# CLK_DIST.net
KiCad netlist of a schematic drawn in Altium Designer
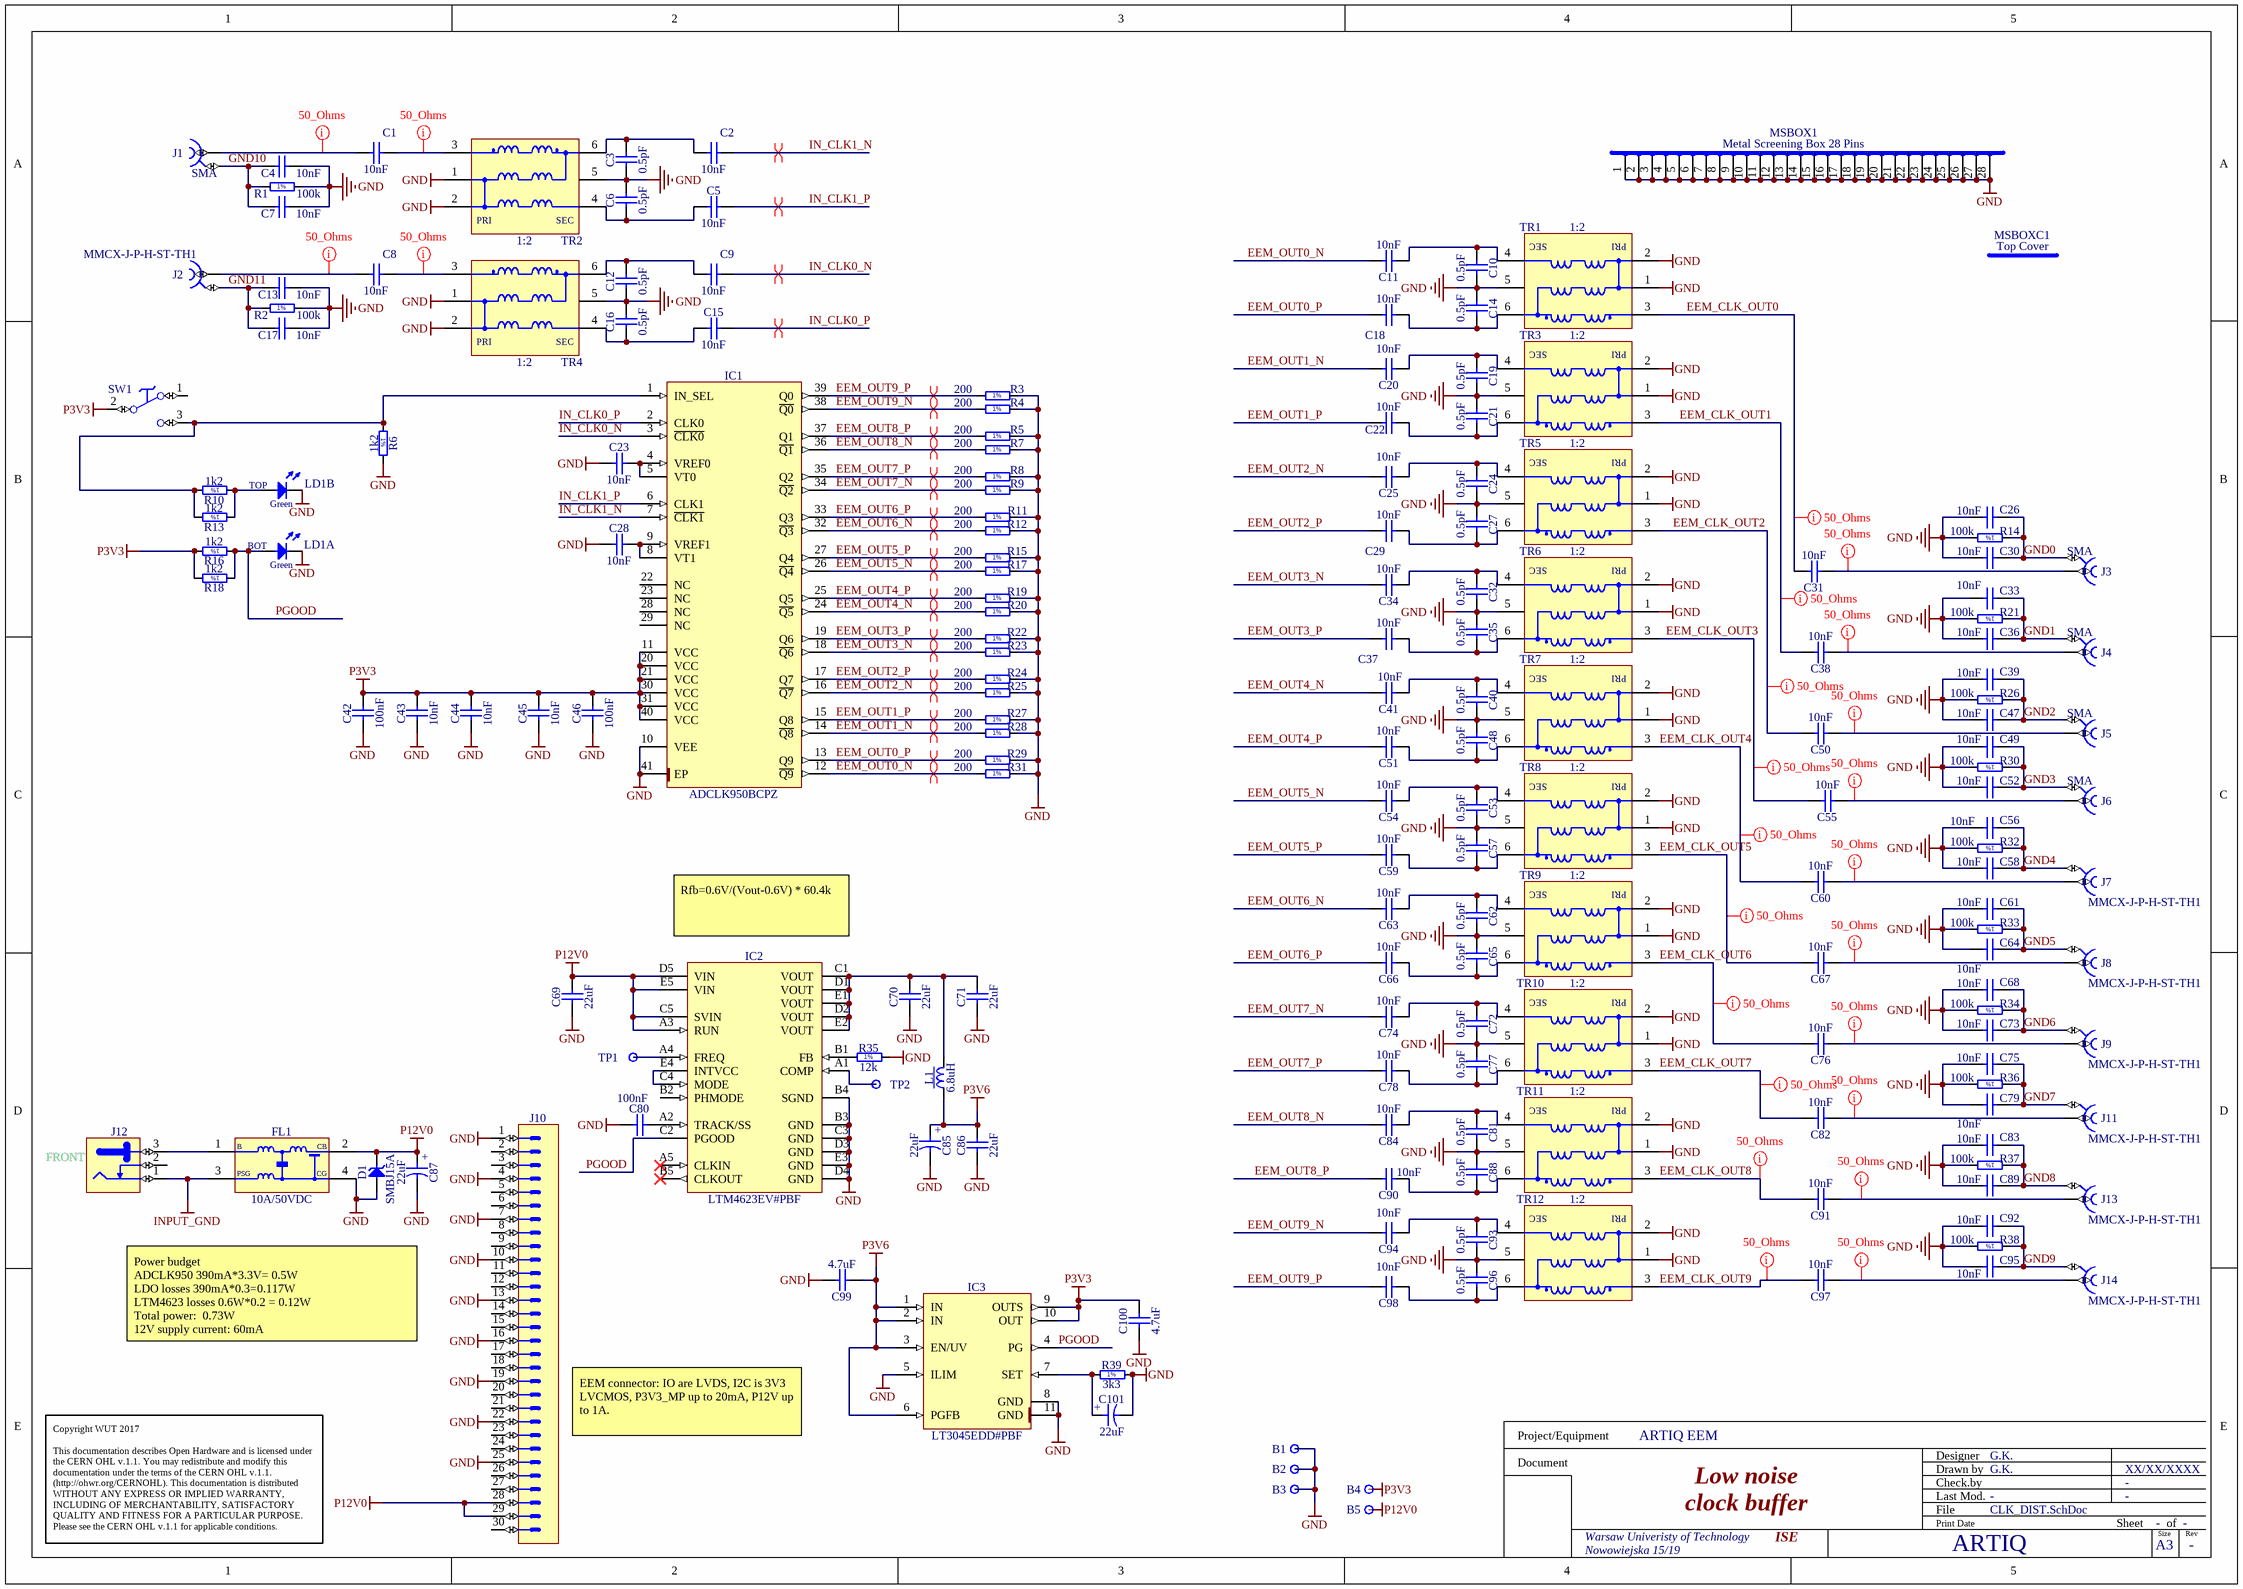
[diagram p0: CLK_DIST.SchDoc]

(export (version "E")
  (design (tool "Eeschema 10.0.6"))
  (components
    (comp (ref "B1")
      (value "Plated Hole")
      (footprint "c130h60")
      (description "Single Terminal Socket")
      (fields (field (name "PART NUMBER") "PLATED_HOLE0.6_PAD1.3") (field (name "AUTHOR") "CERN DEM MR"))
      (libsource (lib "Eletro-mechanical") (part "Single Terminal Socket"))
    )
    (comp (ref "B2")
      (value "Plated Hole")
      (footprint "c130h60")
      (description "Single Terminal Socket")
      (fields (field (name "PART NUMBER") "PLATED_HOLE0.6_PAD1.3") (field (name "AUTHOR") "CERN DEM MR"))
      (libsource (lib "Eletro-mechanical") (part "Single Terminal Socket"))
    )
    (comp (ref "B3")
      (value "Plated Hole")
      (footprint "c130h60")
      (description "Single Terminal Socket")
      (fields (field (name "PART NUMBER") "PLATED_HOLE0.6_PAD1.3") (field (name "AUTHOR") "CERN DEM MR"))
      (libsource (lib "Eletro-mechanical") (part "Single Terminal Socket"))
    )
    (comp (ref "B4")
      (value "Plated Hole")
      (footprint "c130h60")
      (description "Single Terminal Socket")
      (fields (field (name "PART NUMBER") "PLATED_HOLE0.6_PAD1.3") (field (name "AUTHOR") "CERN DEM MR"))
      (libsource (lib "Eletro-mechanical") (part "Single Terminal Socket"))
    )
    (comp (ref "B5")
      (value "Plated Hole")
      (footprint "c130h60")
      (description "Single Terminal Socket")
      (fields (field (name "PART NUMBER") "PLATED_HOLE0.6_PAD1.3") (field (name "AUTHOR") "CERN DEM MR"))
      (libsource (lib "Eletro-mechanical") (part "Single Terminal Socket"))
    )
    (comp (ref "C1")
      (value "10nF")
      (footprint "CAPC1608X87N")
      (description "Non-polarised capacitor")
      (fields
        (field (name "PART NUMBER") "CC0603_10NF_50V_5%_C0G")
        (field (name "VOLTAGE") "50V")
        (field (name "AUTHOR") "CERN DEM JLC")
      )
      (libsource (lib "Capacitors") (part "Capacitor - non polarized"))
    )
    (comp (ref "C2")
      (value "10nF")
      (footprint "CAPC1608X87N")
      (description "Non-polarised capacitor")
      (fields
        (field (name "PART NUMBER") "CC0603_10NF_50V_5%_C0G")
        (field (name "VOLTAGE") "50V")
        (field (name "AUTHOR") "CERN DEM JLC")
      )
      (libsource (lib "Capacitors") (part "Capacitor - non polarized"))
    )
    (comp (ref "C3")
      (value "0.5pF")
      (footprint "CAPC1005X50N")
      (description "Non-polarised capacitor")
      (fields
        (field (name "PART NUMBER") "CC0402_0.5PF_25V_0.05PF_AVX_04023J0R5ABSTR")
        (field (name "VOLTAGE") "25V")
        (field (name "AUTHOR") "CERN DEM JLC")
      )
      (libsource (lib "Capacitors") (part "Capacitor - non polarized"))
    )
    (comp (ref "C4")
      (value "10nF")
      (footprint "CAPC1608X87N")
      (description "Non-polarised capacitor")
      (fields
        (field (name "PART NUMBER") "CC0603_10NF_50V_5%_C0G")
        (field (name "VOLTAGE") "50V")
        (field (name "AUTHOR") "CERN DEM JLC")
      )
      (libsource (lib "Capacitors") (part "Capacitor - non polarized"))
    )
    (comp (ref "C5")
      (value "10nF")
      (footprint "CAPC1608X87N")
      (description "Non-polarised capacitor")
      (fields
        (field (name "PART NUMBER") "CC0603_10NF_50V_5%_C0G")
        (field (name "VOLTAGE") "50V")
        (field (name "AUTHOR") "CERN DEM JLC")
      )
      (libsource (lib "Capacitors") (part "Capacitor - non polarized"))
    )
    (comp (ref "C6")
      (value "0.5pF")
      (footprint "CAPC1005X50N")
      (description "Non-polarised capacitor")
      (fields
        (field (name "PART NUMBER") "CC0402_0.5PF_25V_0.05PF_AVX_04023J0R5ABSTR")
        (field (name "VOLTAGE") "25V")
        (field (name "AUTHOR") "CERN DEM JLC")
      )
      (libsource (lib "Capacitors") (part "Capacitor - non polarized"))
    )
    (comp (ref "C7")
      (value "10nF")
      (footprint "CAPC1608X87N")
      (description "Non-polarised capacitor")
      (fields
        (field (name "PART NUMBER") "CC0603_10NF_50V_5%_C0G")
        (field (name "VOLTAGE") "50V")
        (field (name "AUTHOR") "CERN DEM JLC")
      )
      (libsource (lib "Capacitors") (part "Capacitor - non polarized"))
    )
    (comp (ref "C8")
      (value "10nF")
      (footprint "CAPC1608X87N")
      (description "Non-polarised capacitor")
      (fields
        (field (name "PART NUMBER") "CC0603_10NF_50V_5%_C0G")
        (field (name "VOLTAGE") "50V")
        (field (name "AUTHOR") "CERN DEM JLC")
      )
      (libsource (lib "Capacitors") (part "Capacitor - non polarized"))
    )
    (comp (ref "C9")
      (value "10nF")
      (footprint "CAPC1608X87N")
      (description "Non-polarised capacitor")
      (fields
        (field (name "PART NUMBER") "CC0603_10NF_50V_5%_C0G")
        (field (name "VOLTAGE") "50V")
        (field (name "AUTHOR") "CERN DEM JLC")
      )
      (libsource (lib "Capacitors") (part "Capacitor - non polarized"))
    )
    (comp (ref "C10")
      (value "0.5pF")
      (footprint "CAPC1005X50N")
      (description "Non-polarised capacitor")
      (fields
        (field (name "PART NUMBER") "CC0402_0.5PF_25V_0.05PF_AVX_04023J0R5ABSTR")
        (field (name "VOLTAGE") "25V")
        (field (name "AUTHOR") "CERN DEM JLC")
      )
      (libsource (lib "Capacitors") (part "Capacitor - non polarized"))
    )
    (comp (ref "C11")
      (value "10nF")
      (footprint "CAPC1608X87N")
      (description "Non-polarised capacitor")
      (fields
        (field (name "PART NUMBER") "CC0603_10NF_50V_5%_C0G")
        (field (name "VOLTAGE") "50V")
        (field (name "AUTHOR") "CERN DEM JLC")
      )
      (libsource (lib "Capacitors") (part "Capacitor - non polarized"))
    )
    (comp (ref "C12")
      (value "0.5pF")
      (footprint "CAPC1005X50N")
      (description "Non-polarised capacitor")
      (fields
        (field (name "PART NUMBER") "CC0402_0.5PF_25V_0.05PF_AVX_04023J0R5ABSTR")
        (field (name "VOLTAGE") "25V")
        (field (name "AUTHOR") "CERN DEM JLC")
      )
      (libsource (lib "Capacitors") (part "Capacitor - non polarized"))
    )
    (comp (ref "C13")
      (value "10nF")
      (footprint "CAPC1608X87N")
      (description "Non-polarised capacitor")
      (fields
        (field (name "PART NUMBER") "CC0603_10NF_50V_5%_C0G")
        (field (name "VOLTAGE") "50V")
        (field (name "AUTHOR") "CERN DEM JLC")
      )
      (libsource (lib "Capacitors") (part "Capacitor - non polarized"))
    )
    (comp (ref "C14")
      (value "0.5pF")
      (footprint "CAPC1005X50N")
      (description "Non-polarised capacitor")
      (fields
        (field (name "PART NUMBER") "CC0402_0.5PF_25V_0.05PF_AVX_04023J0R5ABSTR")
        (field (name "VOLTAGE") "25V")
        (field (name "AUTHOR") "CERN DEM JLC")
      )
      (libsource (lib "Capacitors") (part "Capacitor - non polarized"))
    )
    (comp (ref "C15")
      (value "10nF")
      (footprint "CAPC1608X87N")
      (description "Non-polarised capacitor")
      (fields
        (field (name "PART NUMBER") "CC0603_10NF_50V_5%_C0G")
        (field (name "VOLTAGE") "50V")
        (field (name "AUTHOR") "CERN DEM JLC")
      )
      (libsource (lib "Capacitors") (part "Capacitor - non polarized"))
    )
    (comp (ref "C16")
      (value "0.5pF")
      (footprint "CAPC1005X50N")
      (description "Non-polarised capacitor")
      (fields
        (field (name "PART NUMBER") "CC0402_0.5PF_25V_0.05PF_AVX_04023J0R5ABSTR")
        (field (name "VOLTAGE") "25V")
        (field (name "AUTHOR") "CERN DEM JLC")
      )
      (libsource (lib "Capacitors") (part "Capacitor - non polarized"))
    )
    (comp (ref "C17")
      (value "10nF")
      (footprint "CAPC1608X87N")
      (description "Non-polarised capacitor")
      (fields
        (field (name "PART NUMBER") "CC0603_10NF_50V_5%_C0G")
        (field (name "VOLTAGE") "50V")
        (field (name "AUTHOR") "CERN DEM JLC")
      )
      (libsource (lib "Capacitors") (part "Capacitor - non polarized"))
    )
    (comp (ref "C18")
      (value "10nF")
      (footprint "CAPC1608X87N")
      (description "Non-polarised capacitor")
      (fields
        (field (name "PART NUMBER") "CC0603_10NF_50V_5%_C0G")
        (field (name "VOLTAGE") "50V")
        (field (name "AUTHOR") "CERN DEM JLC")
      )
      (libsource (lib "Capacitors") (part "Capacitor - non polarized"))
    )
    (comp (ref "C19")
      (value "0.5pF")
      (footprint "CAPC1005X50N")
      (description "Non-polarised capacitor")
      (fields
        (field (name "PART NUMBER") "CC0402_0.5PF_25V_0.05PF_AVX_04023J0R5ABSTR")
        (field (name "VOLTAGE") "25V")
        (field (name "AUTHOR") "CERN DEM JLC")
      )
      (libsource (lib "Capacitors") (part "Capacitor - non polarized"))
    )
    (comp (ref "C20")
      (value "10nF")
      (footprint "CAPC1608X87N")
      (description "Non-polarised capacitor")
      (fields
        (field (name "PART NUMBER") "CC0603_10NF_50V_5%_C0G")
        (field (name "VOLTAGE") "50V")
        (field (name "AUTHOR") "CERN DEM JLC")
      )
      (libsource (lib "Capacitors") (part "Capacitor - non polarized"))
    )
    (comp (ref "C21")
      (value "0.5pF")
      (footprint "CAPC1005X50N")
      (description "Non-polarised capacitor")
      (fields
        (field (name "PART NUMBER") "CC0402_0.5PF_25V_0.05PF_AVX_04023J0R5ABSTR")
        (field (name "VOLTAGE") "25V")
        (field (name "AUTHOR") "CERN DEM JLC")
      )
      (libsource (lib "Capacitors") (part "Capacitor - non polarized"))
    )
    (comp (ref "C22")
      (value "10nF")
      (footprint "CAPC1608X87N")
      (description "Non-polarised capacitor")
      (fields
        (field (name "PART NUMBER") "CC0603_10NF_50V_5%_C0G")
        (field (name "VOLTAGE") "50V")
        (field (name "AUTHOR") "CERN DEM JLC")
      )
      (libsource (lib "Capacitors") (part "Capacitor - non polarized"))
    )
    (comp (ref "C23")
      (value "10nF")
      (footprint "CAPC1608X87N")
      (description "Non-polarised capacitor")
      (fields
        (field (name "PART NUMBER") "CC0603_10NF_50V_5%_C0G")
        (field (name "VOLTAGE") "50V")
        (field (name "AUTHOR") "CERN DEM JLC")
      )
      (libsource (lib "Capacitors") (part "Capacitor - non polarized"))
    )
    (comp (ref "C24")
      (value "0.5pF")
      (footprint "CAPC1005X50N")
      (description "Non-polarised capacitor")
      (fields
        (field (name "PART NUMBER") "CC0402_0.5PF_25V_0.05PF_AVX_04023J0R5ABSTR")
        (field (name "VOLTAGE") "25V")
        (field (name "AUTHOR") "CERN DEM JLC")
      )
      (libsource (lib "Capacitors") (part "Capacitor - non polarized"))
    )
    (comp (ref "C25")
      (value "10nF")
      (footprint "CAPC1608X87N")
      (description "Non-polarised capacitor")
      (fields
        (field (name "PART NUMBER") "CC0603_10NF_50V_5%_C0G")
        (field (name "VOLTAGE") "50V")
        (field (name "AUTHOR") "CERN DEM JLC")
      )
      (libsource (lib "Capacitors") (part "Capacitor - non polarized"))
    )
    (comp (ref "C26")
      (value "10nF")
      (footprint "CAPC1608X87N")
      (description "Non-polarised capacitor")
      (fields
        (field (name "PART NUMBER") "CC0603_10NF_50V_5%_C0G")
        (field (name "VOLTAGE") "50V")
        (field (name "AUTHOR") "CERN DEM JLC")
      )
      (libsource (lib "Capacitors") (part "Capacitor - non polarized"))
    )
    (comp (ref "C27")
      (value "0.5pF")
      (footprint "CAPC1005X50N")
      (description "Non-polarised capacitor")
      (fields
        (field (name "PART NUMBER") "CC0402_0.5PF_25V_0.05PF_AVX_04023J0R5ABSTR")
        (field (name "VOLTAGE") "25V")
        (field (name "AUTHOR") "CERN DEM JLC")
      )
      (libsource (lib "Capacitors") (part "Capacitor - non polarized"))
    )
    (comp (ref "C28")
      (value "10nF")
      (footprint "CAPC1608X87N")
      (description "Non-polarised capacitor")
      (fields
        (field (name "PART NUMBER") "CC0603_10NF_50V_5%_C0G")
        (field (name "VOLTAGE") "50V")
        (field (name "AUTHOR") "CERN DEM JLC")
      )
      (libsource (lib "Capacitors") (part "Capacitor - non polarized"))
    )
    (comp (ref "C29")
      (value "10nF")
      (footprint "CAPC1608X87N")
      (description "Non-polarised capacitor")
      (fields
        (field (name "PART NUMBER") "CC0603_10NF_50V_5%_C0G")
        (field (name "VOLTAGE") "50V")
        (field (name "AUTHOR") "CERN DEM JLC")
      )
      (libsource (lib "Capacitors") (part "Capacitor - non polarized"))
    )
    (comp (ref "C30")
      (value "10nF")
      (footprint "CAPC1608X87N")
      (description "Non-polarised capacitor")
      (fields
        (field (name "PART NUMBER") "CC0603_10NF_50V_5%_C0G")
        (field (name "VOLTAGE") "50V")
        (field (name "AUTHOR") "CERN DEM JLC")
      )
      (libsource (lib "Capacitors") (part "Capacitor - non polarized"))
    )
    (comp (ref "C31")
      (value "10nF")
      (footprint "CAPC1608X87N")
      (description "Non-polarised capacitor")
      (fields
        (field (name "PART NUMBER") "CC0603_10NF_50V_5%_C0G")
        (field (name "VOLTAGE") "50V")
        (field (name "AUTHOR") "CERN DEM JLC")
      )
      (libsource (lib "Capacitors") (part "Capacitor - non polarized"))
    )
    (comp (ref "C32")
      (value "0.5pF")
      (footprint "CAPC1005X50N")
      (description "Non-polarised capacitor")
      (fields
        (field (name "PART NUMBER") "CC0402_0.5PF_25V_0.05PF_AVX_04023J0R5ABSTR")
        (field (name "VOLTAGE") "25V")
        (field (name "AUTHOR") "CERN DEM JLC")
      )
      (libsource (lib "Capacitors") (part "Capacitor - non polarized"))
    )
    (comp (ref "C33")
      (value "10nF")
      (footprint "CAPC1608X87N")
      (description "Non-polarised capacitor")
      (fields
        (field (name "PART NUMBER") "CC0603_10NF_50V_5%_C0G")
        (field (name "VOLTAGE") "50V")
        (field (name "AUTHOR") "CERN DEM JLC")
      )
      (libsource (lib "Capacitors") (part "Capacitor - non polarized"))
    )
    (comp (ref "C34")
      (value "10nF")
      (footprint "CAPC1608X87N")
      (description "Non-polarised capacitor")
      (fields
        (field (name "PART NUMBER") "CC0603_10NF_50V_5%_C0G")
        (field (name "VOLTAGE") "50V")
        (field (name "AUTHOR") "CERN DEM JLC")
      )
      (libsource (lib "Capacitors") (part "Capacitor - non polarized"))
    )
    (comp (ref "C35")
      (value "0.5pF")
      (footprint "CAPC1005X50N")
      (description "Non-polarised capacitor")
      (fields
        (field (name "PART NUMBER") "CC0402_0.5PF_25V_0.05PF_AVX_04023J0R5ABSTR")
        (field (name "VOLTAGE") "25V")
        (field (name "AUTHOR") "CERN DEM JLC")
      )
      (libsource (lib "Capacitors") (part "Capacitor - non polarized"))
    )
    (comp (ref "C36")
      (value "10nF")
      (footprint "CAPC1608X87N")
      (description "Non-polarised capacitor")
      (fields
        (field (name "PART NUMBER") "CC0603_10NF_50V_5%_C0G")
        (field (name "VOLTAGE") "50V")
        (field (name "AUTHOR") "CERN DEM JLC")
      )
      (libsource (lib "Capacitors") (part "Capacitor - non polarized"))
    )
    (comp (ref "C37")
      (value "10nF")
      (footprint "CAPC1608X87N")
      (description "Non-polarised capacitor")
      (fields
        (field (name "PART NUMBER") "CC0603_10NF_50V_5%_C0G")
        (field (name "VOLTAGE") "50V")
        (field (name "AUTHOR") "CERN DEM JLC")
      )
      (libsource (lib "Capacitors") (part "Capacitor - non polarized"))
    )
    (comp (ref "C38")
      (value "10nF")
      (footprint "CAPC1608X87N")
      (description "Non-polarised capacitor")
      (fields
        (field (name "PART NUMBER") "CC0603_10NF_50V_5%_C0G")
        (field (name "VOLTAGE") "50V")
        (field (name "AUTHOR") "CERN DEM JLC")
      )
      (libsource (lib "Capacitors") (part "Capacitor - non polarized"))
    )
    (comp (ref "C39")
      (value "10nF")
      (footprint "CAPC1608X87N")
      (description "Non-polarised capacitor")
      (fields
        (field (name "PART NUMBER") "CC0603_10NF_50V_5%_C0G")
        (field (name "VOLTAGE") "50V")
        (field (name "AUTHOR") "CERN DEM JLC")
      )
      (libsource (lib "Capacitors") (part "Capacitor - non polarized"))
    )
    (comp (ref "C40")
      (value "0.5pF")
      (footprint "CAPC1005X50N")
      (description "Non-polarised capacitor")
      (fields
        (field (name "PART NUMBER") "CC0402_0.5PF_25V_0.05PF_AVX_04023J0R5ABSTR")
        (field (name "VOLTAGE") "25V")
        (field (name "AUTHOR") "CERN DEM JLC")
      )
      (libsource (lib "Capacitors") (part "Capacitor - non polarized"))
    )
    (comp (ref "C41")
      (value "10nF")
      (footprint "CAPC1608X87N")
      (description "Non-polarised capacitor")
      (fields
        (field (name "PART NUMBER") "CC0603_10NF_50V_5%_C0G")
        (field (name "VOLTAGE") "50V")
        (field (name "AUTHOR") "CERN DEM JLC")
      )
      (libsource (lib "Capacitors") (part "Capacitor - non polarized"))
    )
    (comp (ref "C42")
      (value "100nF")
      (footprint "CAPC1005X55N")
      (description "Non-polarised capacitor")
      (fields
        (field (name "PART NUMBER") "CC0402_100NF_16V_10%_X5R")
        (field (name "VOLTAGE") "16V")
        (field (name "AUTHOR") "CERN DEM JLC")
      )
      (libsource (lib "Capacitors") (part "Capacitor - non polarized"))
    )
    (comp (ref "C43")
      (value "10nF")
      (footprint "CAPC1608X87N")
      (description "Non-polarised capacitor")
      (fields
        (field (name "PART NUMBER") "CC0603_10NF_50V_5%_C0G")
        (field (name "VOLTAGE") "50V")
        (field (name "AUTHOR") "CERN DEM JLC")
      )
      (libsource (lib "Capacitors") (part "Capacitor - non polarized"))
    )
    (comp (ref "C44")
      (value "10nF")
      (footprint "CAPC1608X87N")
      (description "Non-polarised capacitor")
      (fields
        (field (name "PART NUMBER") "CC0603_10NF_50V_5%_C0G")
        (field (name "VOLTAGE") "50V")
        (field (name "AUTHOR") "CERN DEM JLC")
      )
      (libsource (lib "Capacitors") (part "Capacitor - non polarized"))
    )
    (comp (ref "C45")
      (value "10nF")
      (footprint "CAPC1608X87N")
      (description "Non-polarised capacitor")
      (fields
        (field (name "PART NUMBER") "CC0603_10NF_50V_5%_C0G")
        (field (name "VOLTAGE") "50V")
        (field (name "AUTHOR") "CERN DEM JLC")
      )
      (libsource (lib "Capacitors") (part "Capacitor - non polarized"))
    )
    (comp (ref "C46")
      (value "100nF")
      (footprint "CAPC1005X55N")
      (description "Non-polarised capacitor")
      (fields
        (field (name "PART NUMBER") "CC0402_100NF_16V_10%_X5R")
        (field (name "VOLTAGE") "16V")
        (field (name "AUTHOR") "CERN DEM JLC")
      )
      (libsource (lib "Capacitors") (part "Capacitor - non polarized"))
    )
    (comp (ref "C47")
      (value "10nF")
      (footprint "CAPC1608X87N")
      (description "Non-polarised capacitor")
      (fields
        (field (name "PART NUMBER") "CC0603_10NF_50V_5%_C0G")
        (field (name "VOLTAGE") "50V")
        (field (name "AUTHOR") "CERN DEM JLC")
      )
      (libsource (lib "Capacitors") (part "Capacitor - non polarized"))
    )
    (comp (ref "C48")
      (value "0.5pF")
      (footprint "CAPC1005X50N")
      (description "Non-polarised capacitor")
      (fields
        (field (name "PART NUMBER") "CC0402_0.5PF_25V_0.05PF_AVX_04023J0R5ABSTR")
        (field (name "VOLTAGE") "25V")
        (field (name "AUTHOR") "CERN DEM JLC")
      )
      (libsource (lib "Capacitors") (part "Capacitor - non polarized"))
    )
    (comp (ref "C49")
      (value "10nF")
      (footprint "CAPC1608X87N")
      (description "Non-polarised capacitor")
      (fields
        (field (name "PART NUMBER") "CC0603_10NF_50V_5%_C0G")
        (field (name "VOLTAGE") "50V")
        (field (name "AUTHOR") "CERN DEM JLC")
      )
      (libsource (lib "Capacitors") (part "Capacitor - non polarized"))
    )
    (comp (ref "C50")
      (value "10nF")
      (footprint "CAPC1608X87N")
      (description "Non-polarised capacitor")
      (fields
        (field (name "PART NUMBER") "CC0603_10NF_50V_5%_C0G")
        (field (name "VOLTAGE") "50V")
        (field (name "AUTHOR") "CERN DEM JLC")
      )
      (libsource (lib "Capacitors") (part "Capacitor - non polarized"))
    )
    (comp (ref "C51")
      (value "10nF")
      (footprint "CAPC1608X87N")
      (description "Non-polarised capacitor")
      (fields
        (field (name "PART NUMBER") "CC0603_10NF_50V_5%_C0G")
        (field (name "VOLTAGE") "50V")
        (field (name "AUTHOR") "CERN DEM JLC")
      )
      (libsource (lib "Capacitors") (part "Capacitor - non polarized"))
    )
    (comp (ref "C52")
      (value "10nF")
      (footprint "CAPC1608X87N")
      (description "Non-polarised capacitor")
      (fields
        (field (name "PART NUMBER") "CC0603_10NF_50V_5%_C0G")
        (field (name "VOLTAGE") "50V")
        (field (name "AUTHOR") "CERN DEM JLC")
      )
      (libsource (lib "Capacitors") (part "Capacitor - non polarized"))
    )
    (comp (ref "C53")
      (value "0.5pF")
      (footprint "CAPC1005X50N")
      (description "Non-polarised capacitor")
      (fields
        (field (name "PART NUMBER") "CC0402_0.5PF_25V_0.05PF_AVX_04023J0R5ABSTR")
        (field (name "VOLTAGE") "25V")
        (field (name "AUTHOR") "CERN DEM JLC")
      )
      (libsource (lib "Capacitors") (part "Capacitor - non polarized"))
    )
    (comp (ref "C54")
      (value "10nF")
      (footprint "CAPC1608X87N")
      (description "Non-polarised capacitor")
      (fields
        (field (name "PART NUMBER") "CC0603_10NF_50V_5%_C0G")
        (field (name "VOLTAGE") "50V")
        (field (name "AUTHOR") "CERN DEM JLC")
      )
      (libsource (lib "Capacitors") (part "Capacitor - non polarized"))
    )
    (comp (ref "C55")
      (value "10nF")
      (footprint "CAPC1608X87N")
      (description "Non-polarised capacitor")
      (fields
        (field (name "PART NUMBER") "CC0603_10NF_50V_5%_C0G")
        (field (name "VOLTAGE") "50V")
        (field (name "AUTHOR") "CERN DEM JLC")
      )
      (libsource (lib "Capacitors") (part "Capacitor - non polarized"))
    )
    (comp (ref "C56")
      (value "10nF")
      (footprint "CAPC1608X87N")
      (description "Non-polarised capacitor")
      (fields
        (field (name "PART NUMBER") "CC0603_10NF_50V_5%_C0G")
        (field (name "VOLTAGE") "50V")
        (field (name "AUTHOR") "CERN DEM JLC")
      )
      (libsource (lib "Capacitors") (part "Capacitor - non polarized"))
    )
    (comp (ref "C57")
      (value "0.5pF")
      (footprint "CAPC1005X50N")
      (description "Non-polarised capacitor")
      (fields
        (field (name "PART NUMBER") "CC0402_0.5PF_25V_0.05PF_AVX_04023J0R5ABSTR")
        (field (name "VOLTAGE") "25V")
        (field (name "AUTHOR") "CERN DEM JLC")
      )
      (libsource (lib "Capacitors") (part "Capacitor - non polarized"))
    )
    (comp (ref "C58")
      (value "10nF")
      (footprint "CAPC1608X87N")
      (description "Non-polarised capacitor")
      (fields
        (field (name "PART NUMBER") "CC0603_10NF_50V_5%_C0G")
        (field (name "VOLTAGE") "50V")
        (field (name "AUTHOR") "CERN DEM JLC")
      )
      (libsource (lib "Capacitors") (part "Capacitor - non polarized"))
    )
    (comp (ref "C59")
      (value "10nF")
      (footprint "CAPC1608X87N")
      (description "Non-polarised capacitor")
      (fields
        (field (name "PART NUMBER") "CC0603_10NF_50V_5%_C0G")
        (field (name "VOLTAGE") "50V")
        (field (name "AUTHOR") "CERN DEM JLC")
      )
      (libsource (lib "Capacitors") (part "Capacitor - non polarized"))
    )
    (comp (ref "C60")
      (value "10nF")
      (footprint "CAPC1608X87N")
      (description "Non-polarised capacitor")
      (fields
        (field (name "PART NUMBER") "CC0603_10NF_50V_5%_C0G")
        (field (name "VOLTAGE") "50V")
        (field (name "AUTHOR") "CERN DEM JLC")
      )
      (libsource (lib "Capacitors") (part "Capacitor - non polarized"))
    )
    (comp (ref "C61")
      (value "10nF")
      (footprint "CAPC1608X87N")
      (description "Non-polarised capacitor")
      (fields
        (field (name "PART NUMBER") "CC0603_10NF_50V_5%_C0G")
        (field (name "VOLTAGE") "50V")
        (field (name "AUTHOR") "CERN DEM JLC")
      )
      (libsource (lib "Capacitors") (part "Capacitor - non polarized"))
    )
    (comp (ref "C62")
      (value "0.5pF")
      (footprint "CAPC1005X50N")
      (description "Non-polarised capacitor")
      (fields
        (field (name "PART NUMBER") "CC0402_0.5PF_25V_0.05PF_AVX_04023J0R5ABSTR")
        (field (name "VOLTAGE") "25V")
        (field (name "AUTHOR") "CERN DEM JLC")
      )
      (libsource (lib "Capacitors") (part "Capacitor - non polarized"))
    )
    (comp (ref "C63")
      (value "10nF")
      (footprint "CAPC1608X87N")
      (description "Non-polarised capacitor")
      (fields
        (field (name "PART NUMBER") "CC0603_10NF_50V_5%_C0G")
        (field (name "VOLTAGE") "50V")
        (field (name "AUTHOR") "CERN DEM JLC")
      )
      (libsource (lib "Capacitors") (part "Capacitor - non polarized"))
    )
    (comp (ref "C64")
      (value "10nF")
      (footprint "CAPC1608X87N")
      (description "Non-polarised capacitor")
      (fields
        (field (name "PART NUMBER") "CC0603_10NF_50V_5%_C0G")
        (field (name "VOLTAGE") "50V")
        (field (name "AUTHOR") "CERN DEM JLC")
      )
      (libsource (lib "Capacitors") (part "Capacitor - non polarized"))
    )
    (comp (ref "C65")
      (value "0.5pF")
      (footprint "CAPC1005X50N")
      (description "Non-polarised capacitor")
      (fields
        (field (name "PART NUMBER") "CC0402_0.5PF_25V_0.05PF_AVX_04023J0R5ABSTR")
        (field (name "VOLTAGE") "25V")
        (field (name "AUTHOR") "CERN DEM JLC")
      )
      (libsource (lib "Capacitors") (part "Capacitor - non polarized"))
    )
    (comp (ref "C66")
      (value "10nF")
      (footprint "CAPC1608X87N")
      (description "Non-polarised capacitor")
      (fields
        (field (name "PART NUMBER") "CC0603_10NF_50V_5%_C0G")
        (field (name "VOLTAGE") "50V")
        (field (name "AUTHOR") "CERN DEM JLC")
      )
      (libsource (lib "Capacitors") (part "Capacitor - non polarized"))
    )
    (comp (ref "C67")
      (value "10nF")
      (footprint "CAPC1608X87N")
      (description "Non-polarised capacitor")
      (fields
        (field (name "PART NUMBER") "CC0603_10NF_50V_5%_C0G")
        (field (name "VOLTAGE") "50V")
        (field (name "AUTHOR") "CERN DEM JLC")
      )
      (libsource (lib "Capacitors") (part "Capacitor - non polarized"))
    )
    (comp (ref "C68")
      (value "10nF")
      (footprint "CAPC1608X87N")
      (description "Non-polarised capacitor")
      (fields
        (field (name "PART NUMBER") "CC0603_10NF_50V_5%_C0G")
        (field (name "VOLTAGE") "50V")
        (field (name "AUTHOR") "CERN DEM JLC")
      )
      (libsource (lib "Capacitors") (part "Capacitor - non polarized"))
    )
    (comp (ref "C69")
      (value "22uF")
      (footprint "CAPC2012X135N")
      (description "Non-polarised capacitor")
      (fields
        (field (name "PART NUMBER") "CC0805_22UF_16V_10%_X5R")
        (field (name "VOLTAGE") "16V")
        (field (name "AUTHOR") "CERN DEM JLC")
      )
      (libsource (lib "Capacitors") (part "Capacitor - non polarized"))
    )
    (comp (ref "C70")
      (value "22uF")
      (footprint "CAPC2012X135N")
      (description "Non-polarised capacitor")
      (fields
        (field (name "PART NUMBER") "CC0805_22UF_16V_10%_X5R")
        (field (name "VOLTAGE") "16V")
        (field (name "AUTHOR") "CERN DEM JLC")
      )
      (libsource (lib "Capacitors") (part "Capacitor - non polarized"))
    )
    (comp (ref "C71")
      (value "22uF")
      (footprint "CAPC2012X135N")
      (description "Non-polarised capacitor")
      (fields
        (field (name "PART NUMBER") "CC0805_22UF_16V_10%_X5R")
        (field (name "VOLTAGE") "16V")
        (field (name "AUTHOR") "CERN DEM JLC")
      )
      (libsource (lib "Capacitors") (part "Capacitor - non polarized"))
    )
    (comp (ref "C72")
      (value "0.5pF")
      (footprint "CAPC1005X50N")
      (description "Non-polarised capacitor")
      (fields
        (field (name "PART NUMBER") "CC0402_0.5PF_25V_0.05PF_AVX_04023J0R5ABSTR")
        (field (name "VOLTAGE") "25V")
        (field (name "AUTHOR") "CERN DEM JLC")
      )
      (libsource (lib "Capacitors") (part "Capacitor - non polarized"))
    )
    (comp (ref "C73")
      (value "10nF")
      (footprint "CAPC1608X87N")
      (description "Non-polarised capacitor")
      (fields
        (field (name "PART NUMBER") "CC0603_10NF_50V_5%_C0G")
        (field (name "VOLTAGE") "50V")
        (field (name "AUTHOR") "CERN DEM JLC")
      )
      (libsource (lib "Capacitors") (part "Capacitor - non polarized"))
    )
    (comp (ref "C74")
      (value "10nF")
      (footprint "CAPC1608X87N")
      (description "Non-polarised capacitor")
      (fields
        (field (name "PART NUMBER") "CC0603_10NF_50V_5%_C0G")
        (field (name "VOLTAGE") "50V")
        (field (name "AUTHOR") "CERN DEM JLC")
      )
      (libsource (lib "Capacitors") (part "Capacitor - non polarized"))
    )
    (comp (ref "C75")
      (value "10nF")
      (footprint "CAPC1608X87N")
      (description "Non-polarised capacitor")
      (fields
        (field (name "PART NUMBER") "CC0603_10NF_50V_5%_C0G")
        (field (name "VOLTAGE") "50V")
        (field (name "AUTHOR") "CERN DEM JLC")
      )
      (libsource (lib "Capacitors") (part "Capacitor - non polarized"))
    )
    (comp (ref "C76")
      (value "10nF")
      (footprint "CAPC1608X87N")
      (description "Non-polarised capacitor")
      (fields
        (field (name "PART NUMBER") "CC0603_10NF_50V_5%_C0G")
        (field (name "VOLTAGE") "50V")
        (field (name "AUTHOR") "CERN DEM JLC")
      )
      (libsource (lib "Capacitors") (part "Capacitor - non polarized"))
    )
    (comp (ref "C77")
      (value "0.5pF")
      (footprint "CAPC1005X50N")
      (description "Non-polarised capacitor")
      (fields
        (field (name "PART NUMBER") "CC0402_0.5PF_25V_0.05PF_AVX_04023J0R5ABSTR")
        (field (name "VOLTAGE") "25V")
        (field (name "AUTHOR") "CERN DEM JLC")
      )
      (libsource (lib "Capacitors") (part "Capacitor - non polarized"))
    )
    (comp (ref "C78")
      (value "10nF")
      (footprint "CAPC1608X87N")
      (description "Non-polarised capacitor")
      (fields
        (field (name "PART NUMBER") "CC0603_10NF_50V_5%_C0G")
        (field (name "VOLTAGE") "50V")
        (field (name "AUTHOR") "CERN DEM JLC")
      )
      (libsource (lib "Capacitors") (part "Capacitor - non polarized"))
    )
    (comp (ref "C79")
      (value "10nF")
      (footprint "CAPC1608X87N")
      (description "Non-polarised capacitor")
      (fields
        (field (name "PART NUMBER") "CC0603_10NF_50V_5%_C0G")
        (field (name "VOLTAGE") "50V")
        (field (name "AUTHOR") "CERN DEM JLC")
      )
      (libsource (lib "Capacitors") (part "Capacitor - non polarized"))
    )
    (comp (ref "C80")
      (value "100nF")
      (footprint "CAPC1005X55N")
      (description "Non-polarised capacitor")
      (fields
        (field (name "PART NUMBER") "CC0402_100NF_16V_10%_X5R")
        (field (name "VOLTAGE") "16V")
        (field (name "AUTHOR") "CERN DEM JLC")
      )
      (libsource (lib "Capacitors") (part "Capacitor - non polarized"))
    )
    (comp (ref "C81")
      (value "0.5pF")
      (footprint "CAPC1005X50N")
      (description "Non-polarised capacitor")
      (fields
        (field (name "PART NUMBER") "CC0402_0.5PF_25V_0.05PF_AVX_04023J0R5ABSTR")
        (field (name "VOLTAGE") "25V")
        (field (name "AUTHOR") "CERN DEM JLC")
      )
      (libsource (lib "Capacitors") (part "Capacitor - non polarized"))
    )
    (comp (ref "C82")
      (value "10nF")
      (footprint "CAPC1608X87N")
      (description "Non-polarised capacitor")
      (fields
        (field (name "PART NUMBER") "CC0603_10NF_50V_5%_C0G")
        (field (name "VOLTAGE") "50V")
        (field (name "AUTHOR") "CERN DEM JLC")
      )
      (libsource (lib "Capacitors") (part "Capacitor - non polarized"))
    )
    (comp (ref "C83")
      (value "10nF")
      (footprint "CAPC1608X87N")
      (description "Non-polarised capacitor")
      (fields
        (field (name "PART NUMBER") "CC0603_10NF_50V_5%_C0G")
        (field (name "VOLTAGE") "50V")
        (field (name "AUTHOR") "CERN DEM JLC")
      )
      (libsource (lib "Capacitors") (part "Capacitor - non polarized"))
    )
    (comp (ref "C84")
      (value "10nF")
      (footprint "CAPC1608X87N")
      (description "Non-polarised capacitor")
      (fields
        (field (name "PART NUMBER") "CC0603_10NF_50V_5%_C0G")
        (field (name "VOLTAGE") "50V")
        (field (name "AUTHOR") "CERN DEM JLC")
      )
      (libsource (lib "Capacitors") (part "Capacitor - non polarized"))
    )
    (comp (ref "C85")
      (value "22uF")
      (footprint "CAPMP3216X180N")
      (description "Polarised capacitor")
      (fields
        (field (name "PART NUMBER") "CTE3216-18_22UF_6.3V_10%_LESR0900")
        (field (name "VOLTAGE") "6.3V")
        (field (name "AUTHOR") "CERN DEM JLC")
      )
      (libsource (lib "Capacitors") (part "Capacitor - polarized"))
    )
    (comp (ref "C86")
      (value "22uF")
      (footprint "CAPC2012X135N")
      (description "Non-polarised capacitor")
      (fields
        (field (name "PART NUMBER") "CC0805_22UF_16V_10%_X5R")
        (field (name "VOLTAGE") "16V")
        (field (name "AUTHOR") "CERN DEM JLC")
      )
      (libsource (lib "Capacitors") (part "Capacitor - non polarized"))
    )
    (comp (ref "C87")
      (value "22uF")
      (footprint "CAPAE530X540N")
      (description "Polarised capacitor")
      (fields
        (field (name "PART NUMBER") "CAE530-540_22UF_16V_20%")
        (field (name "VOLTAGE") "16V")
        (field (name "AUTHOR") "CERN DEM JLC")
      )
      (libsource (lib "Capacitors") (part "Capacitor - polarized"))
    )
    (comp (ref "C88")
      (value "0.5pF")
      (footprint "CAPC1005X50N")
      (description "Non-polarised capacitor")
      (fields
        (field (name "PART NUMBER") "CC0402_0.5PF_25V_0.05PF_AVX_04023J0R5ABSTR")
        (field (name "VOLTAGE") "25V")
        (field (name "AUTHOR") "CERN DEM JLC")
      )
      (libsource (lib "Capacitors") (part "Capacitor - non polarized"))
    )
    (comp (ref "C89")
      (value "10nF")
      (footprint "CAPC1608X87N")
      (description "Non-polarised capacitor")
      (fields
        (field (name "PART NUMBER") "CC0603_10NF_50V_5%_C0G")
        (field (name "VOLTAGE") "50V")
        (field (name "AUTHOR") "CERN DEM JLC")
      )
      (libsource (lib "Capacitors") (part "Capacitor - non polarized"))
    )
    (comp (ref "C90")
      (value "10nF")
      (footprint "CAPC1608X87N")
      (description "Non-polarised capacitor")
      (fields
        (field (name "PART NUMBER") "CC0603_10NF_50V_5%_C0G")
        (field (name "VOLTAGE") "50V")
        (field (name "AUTHOR") "CERN DEM JLC")
      )
      (libsource (lib "Capacitors") (part "Capacitor - non polarized"))
    )
    (comp (ref "C91")
      (value "10nF")
      (footprint "CAPC1608X87N")
      (description "Non-polarised capacitor")
      (fields
        (field (name "PART NUMBER") "CC0603_10NF_50V_5%_C0G")
        (field (name "VOLTAGE") "50V")
        (field (name "AUTHOR") "CERN DEM JLC")
      )
      (libsource (lib "Capacitors") (part "Capacitor - non polarized"))
    )
    (comp (ref "C92")
      (value "10nF")
      (footprint "CAPC1608X87N")
      (description "Non-polarised capacitor")
      (fields
        (field (name "PART NUMBER") "CC0603_10NF_50V_5%_C0G")
        (field (name "VOLTAGE") "50V")
        (field (name "AUTHOR") "CERN DEM JLC")
      )
      (libsource (lib "Capacitors") (part "Capacitor - non polarized"))
    )
    (comp (ref "C93")
      (value "0.5pF")
      (footprint "CAPC1005X50N")
      (description "Non-polarised capacitor")
      (fields
        (field (name "PART NUMBER") "CC0402_0.5PF_25V_0.05PF_AVX_04023J0R5ABSTR")
        (field (name "VOLTAGE") "25V")
        (field (name "AUTHOR") "CERN DEM JLC")
      )
      (libsource (lib "Capacitors") (part "Capacitor - non polarized"))
    )
    (comp (ref "C94")
      (value "10nF")
      (footprint "CAPC1608X87N")
      (description "Non-polarised capacitor")
      (fields
        (field (name "PART NUMBER") "CC0603_10NF_50V_5%_C0G")
        (field (name "VOLTAGE") "50V")
        (field (name "AUTHOR") "CERN DEM JLC")
      )
      (libsource (lib "Capacitors") (part "Capacitor - non polarized"))
    )
    (comp (ref "C95")
      (value "10nF")
      (footprint "CAPC1608X87N")
      (description "Non-polarised capacitor")
      (fields
        (field (name "PART NUMBER") "CC0603_10NF_50V_5%_C0G")
        (field (name "VOLTAGE") "50V")
        (field (name "AUTHOR") "CERN DEM JLC")
      )
      (libsource (lib "Capacitors") (part "Capacitor - non polarized"))
    )
    (comp (ref "C96")
      (value "0.5pF")
      (footprint "CAPC1005X50N")
      (description "Non-polarised capacitor")
      (fields
        (field (name "PART NUMBER") "CC0402_0.5PF_25V_0.05PF_AVX_04023J0R5ABSTR")
        (field (name "VOLTAGE") "25V")
        (field (name "AUTHOR") "CERN DEM JLC")
      )
      (libsource (lib "Capacitors") (part "Capacitor - non polarized"))
    )
    (comp (ref "C97")
      (value "10nF")
      (footprint "CAPC1608X87N")
      (description "Non-polarised capacitor")
      (fields
        (field (name "PART NUMBER") "CC0603_10NF_50V_5%_C0G")
        (field (name "VOLTAGE") "50V")
        (field (name "AUTHOR") "CERN DEM JLC")
      )
      (libsource (lib "Capacitors") (part "Capacitor - non polarized"))
    )
    (comp (ref "C98")
      (value "10nF")
      (footprint "CAPC1608X87N")
      (description "Non-polarised capacitor")
      (fields
        (field (name "PART NUMBER") "CC0603_10NF_50V_5%_C0G")
        (field (name "VOLTAGE") "50V")
        (field (name "AUTHOR") "CERN DEM JLC")
      )
      (libsource (lib "Capacitors") (part "Capacitor - non polarized"))
    )
    (comp (ref "C99")
      (value "4.7uF")
      (footprint "CAPC1608X90N")
      (description "Non-polarised capacitor")
      (fields
        (field (name "PART NUMBER") "CC0603_4.7UF_25V_10%_X5R")
        (field (name "VOLTAGE") "25V")
        (field (name "AUTHOR") "CERN DEM JLC")
      )
      (libsource (lib "Capacitors") (part "Capacitor - non polarized"))
    )
    (comp (ref "C100")
      (value "4.7uF")
      (footprint "CAPC1608X90N")
      (description "Non-polarised capacitor")
      (fields
        (field (name "PART NUMBER") "CC0603_4.7UF_25V_10%_X5R")
        (field (name "VOLTAGE") "25V")
        (field (name "AUTHOR") "CERN DEM JLC")
      )
      (libsource (lib "Capacitors") (part "Capacitor - non polarized"))
    )
    (comp (ref "C101")
      (value "22uF")
      (footprint "CAPMP3216X180N")
      (description "Polarised capacitor")
      (fields
        (field (name "PART NUMBER") "CTE3216-18_22UF_6.3V_10%_LESR0900")
        (field (name "VOLTAGE") "6.3V")
        (field (name "AUTHOR") "CERN DEM JLC")
      )
      (libsource (lib "Capacitors") (part "Capacitor - polarized"))
    )
    (comp (ref "D1")
      (value "SMBJ15A")
      (footprint "DIOM5336X265N")
      (description "Zener Diode")
      (fields
        (field (name "VOLTAGE") "15V")
        (field (name "POWER") "600W")
        (field (name "AUTHOR") "CERN DEM JLC")
      )
      (libsource (lib "ICs And Semiconductors") (part "Diode Zener"))
    )
    (comp (ref "FL1")
      (value "10A/50VDC")
      (footprint "FIL_MURATA_BNX02")
      (description "Block Type EMIFIL (LC Combined)")
      (fields
        (field (name "PART NUMBER") "FIL_MURATA_BNX022-01L")
        (field (name "MANUFACTURER") "MURATA")
        (field (name "AUTHOR") "CERN DEM JLC")
      )
      (libsource (lib "Inductors & Transformers") (part "FIL_MURATA_BNX02"))
    )
    (comp (ref "IC1")
      (value "ADCLK950BCPZ")
      (footprint "QFN50P600X600X100-41N-S305")
      (description "Two Selectable Inputs, 10 LVPECL Outputs, SiGe Clock Fanout Buffer")
      (fields (field (name "MANUFACTURER") "ANALOG DEVICES") (field (name "AUTHOR") "CERN DEM BC"))
      (libsource (lib "ICs And Semiconductors") (part "ADCLK950"))
    )
    (comp (ref "IC2")
      (value "LTM4623EV#PBF")
      (footprint "LGA25C127P5X5_625X625X192")
      (description "4V-20V to 0.6V-5.5V, Iout 3A Step-Down DC/DC uModule Regulator")
      (fields (field (name "MANUFACTURER") "LINEAR TECHNOLOGY") (field (name "AUTHOR") "CERN DEM JMW"))
      (libsource (lib "ICs And Semiconductors") (part "LTM4623"))
    )
    (comp (ref "IC3")
      (value "LT3045EDD#PBF")
      (footprint "SON50P300X300X80-11N-R175X248")
      (description "20V, 500mA, Ultralow Noise, Ultrahigh PSRR Linear Regulator")
      (fields (field (name "MANUFACTURER") "LINEAR TECHNOLOGY") (field (name "AUTHOR") "CERN DEM JLC"))
      (libsource (lib "ICs And Semiconductors") (part "LT3045EDD"))
    )
    (comp (ref "J1")
      (value "SMA")
      (footprint "RF249BT0050GHDW")
      (description "50 Ohm Through Hole SMA Right Angle PCB Jack")
      (fields
        (field (name "PART NUMBER") "AdamTech_RF249BT0050GHDW")
        (field (name "MANUFACTURER") "AdamTech")
        (field (name "AUTHOR") "GK")
      )
      (libsource (lib "LIBRARY_SCH") (part "CON_SMA_RF249BT0050GHDW"))
    )
    (comp (ref "J2")
      (value "MMCX-J-P-H-ST-TH1")
      (footprint "SAMTEC_MMCX-J-P-H-ST-TH1")
      (fields
        (field (name "PART NUMBER") "SAMTEC_MMCX-J-P-H-ST-TH1")
        (field (name "MANUFACTURER") "SAMTEC")
        (field (name "AUTHOR") "CERN DEM JLC")
      )
      (libsource (lib "Connectors") (part "Coax_1Female_1Shield"))
    )
    (comp (ref "J3")
      (value "SMA")
      (footprint "RF249BT0050GHDW")
      (description "50 Ohm Through Hole SMA Right Angle PCB Jack")
      (fields
        (field (name "PART NUMBER") "AdamTech_RF249BT0050GHDW")
        (field (name "MANUFACTURER") "AdamTech")
        (field (name "AUTHOR") "GK")
      )
      (libsource (lib "LIBRARY_SCH") (part "CON_SMA_RF249BT0050GHDW"))
    )
    (comp (ref "J4")
      (value "SMA")
      (footprint "RF249BT0050GHDW")
      (description "50 Ohm Through Hole SMA Right Angle PCB Jack")
      (fields
        (field (name "PART NUMBER") "AdamTech_RF249BT0050GHDW")
        (field (name "MANUFACTURER") "AdamTech")
        (field (name "AUTHOR") "GK")
      )
      (libsource (lib "LIBRARY_SCH") (part "CON_SMA_RF249BT0050GHDW"))
    )
    (comp (ref "J5")
      (value "SMA")
      (footprint "RF249BT0050GHDW")
      (description "50 Ohm Through Hole SMA Right Angle PCB Jack")
      (fields
        (field (name "PART NUMBER") "AdamTech_RF249BT0050GHDW")
        (field (name "MANUFACTURER") "AdamTech")
        (field (name "AUTHOR") "GK")
      )
      (libsource (lib "LIBRARY_SCH") (part "CON_SMA_RF249BT0050GHDW"))
    )
    (comp (ref "J6")
      (value "SMA")
      (footprint "RF249BT0050GHDW")
      (description "50 Ohm Through Hole SMA Right Angle PCB Jack")
      (fields
        (field (name "PART NUMBER") "AdamTech_RF249BT0050GHDW")
        (field (name "MANUFACTURER") "AdamTech")
        (field (name "AUTHOR") "GK")
      )
      (libsource (lib "LIBRARY_SCH") (part "CON_SMA_RF249BT0050GHDW"))
    )
    (comp (ref "J7")
      (value "MMCX-J-P-H-ST-TH1")
      (footprint "SAMTEC_MMCX-J-P-H-ST-TH1")
      (fields
        (field (name "PART NUMBER") "SAMTEC_MMCX-J-P-H-ST-TH1")
        (field (name "MANUFACTURER") "SAMTEC")
        (field (name "AUTHOR") "CERN DEM JLC")
      )
      (libsource (lib "Connectors") (part "Coax_1Female_1Shield"))
    )
    (comp (ref "J8")
      (value "MMCX-J-P-H-ST-TH1")
      (footprint "SAMTEC_MMCX-J-P-H-ST-TH1")
      (fields
        (field (name "PART NUMBER") "SAMTEC_MMCX-J-P-H-ST-TH1")
        (field (name "MANUFACTURER") "SAMTEC")
        (field (name "AUTHOR") "CERN DEM JLC")
      )
      (libsource (lib "Connectors") (part "Coax_1Female_1Shield"))
    )
    (comp (ref "J9")
      (value "MMCX-J-P-H-ST-TH1")
      (footprint "SAMTEC_MMCX-J-P-H-ST-TH1")
      (fields
        (field (name "PART NUMBER") "SAMTEC_MMCX-J-P-H-ST-TH1")
        (field (name "MANUFACTURER") "SAMTEC")
        (field (name "AUTHOR") "CERN DEM JLC")
      )
      (libsource (lib "Connectors") (part "Coax_1Female_1Shield"))
    )
    (comp (ref "J10")
      (value "~")
      (footprint "3M_N2530-6002RB")
      (description "Connector 30 Male")
      (fields
        (field (name "PART NUMBER") "3M_N2530-6002RB")
        (field (name "MANUFACTURER") "3M")
        (field (name "AUTHOR") "CERN DEM JLC")
      )
      (libsource (lib "Connectors") (part "Connector 30 Male"))
    )
    (comp (ref "J11")
      (value "MMCX-J-P-H-ST-TH1")
      (footprint "SAMTEC_MMCX-J-P-H-ST-TH1")
      (fields
        (field (name "PART NUMBER") "SAMTEC_MMCX-J-P-H-ST-TH1")
        (field (name "MANUFACTURER") "SAMTEC")
        (field (name "AUTHOR") "CERN DEM JLC")
      )
      (libsource (lib "Connectors") (part "Coax_1Female_1Shield"))
    )
    (comp (ref "J12")
      (value "Jack")
      (footprint "SWITCHCRAFT_L712RA")
      (description "24V /3. 5A, 2.1mm Diameter Pin, SMD DC Power Supply Connector With  Break Contact")
      (fields
        (field (name "PART NUMBER") "SWITCHCRAFT_712RA")
        (field (name "MANUFACTURER") "SWITCHCRAFT")
        (field (name "AUTHOR") "GK")
      )
      (libsource (lib "LIBRARY_SCH") (part "CON_DC_5A_THT_RA"))
    )
    (comp (ref "J13")
      (value "MMCX-J-P-H-ST-TH1")
      (footprint "SAMTEC_MMCX-J-P-H-ST-TH1")
      (fields
        (field (name "PART NUMBER") "SAMTEC_MMCX-J-P-H-ST-TH1")
        (field (name "MANUFACTURER") "SAMTEC")
        (field (name "AUTHOR") "CERN DEM JLC")
      )
      (libsource (lib "Connectors") (part "Coax_1Female_1Shield"))
    )
    (comp (ref "J14")
      (value "MMCX-J-P-H-ST-TH1")
      (footprint "SAMTEC_MMCX-J-P-H-ST-TH1")
      (fields
        (field (name "PART NUMBER") "SAMTEC_MMCX-J-P-H-ST-TH1")
        (field (name "MANUFACTURER") "SAMTEC")
        (field (name "AUTHOR") "CERN DEM JLC")
      )
      (libsource (lib "Connectors") (part "Coax_1Female_1Shield"))
    )
    (comp (ref "L1")
      (value "6.8uH")
      (footprint "IND_COILCRAFT_XAL4030")
      (description "Inductor With Core")
      (fields
        (field (name "PART NUMBER") "IND_6.8UH_20%_COILCRAFT_XAL4030")
        (field (name "POWER") "3A")
        (field (name "AUTHOR") "CERN DEM MR")
      )
      (libsource (lib "Inductors & Transformers") (part "Inductor With Magnetic core"))
    )
    (comp (ref "LD1")
      (value "Green/Green")
      (footprint "LED_DIALIGHT_571-0122F")
      (description "LED x2 Green 1C2A-BOT_3C4A-TOP")
      (fields
        (field (name "PART NUMBER") "LED_DIALIGHT_571-0122F")
        (field (name "MANUFACTURER") "DIALIGHT")
        (field (name "AUTHOR") "CERN DEM JLC")
      )
      (libsource (lib "ICs And Semiconductors") (part "LED x2 Green 1C2A-BOT_3C4A-TOP"))
    )
    (comp (ref "MSBOX1")
      (value "Metal Screening Box 28 Pins")
      (footprint "MSBOX_LAIRD_BMI-S-207-F")
      (fields
        (field (name "PART NUMBER") "MSBOX_LAIRD_BMI-S-207-F")
        (field (name "MANUFACTURER") "LAIRD")
        (field (name "MANUFACTURER PART NUMBER") "BMI-S-207-F")
        (field (name "AUTHOR") "CERN DEM JLC")
      )
      (libsource (lib "Eletro-mechanical") (part "Metal Screening Box - 28 pins"))
    )
    (comp (ref "MSBOXC1")
      (value "Top Cover")
      (footprint "MSBOX_LAIRD_BMI-S-207-C")
      (description "Metal Screening Box - Top Cover 0 Pin")
      (fields
        (field (name "PART NUMBER") "MSBOX_LAIRD_BMI-S-207-C")
        (field (name "MANUFACTURER") "LAIRD")
        (field (name "AUTHOR") "CERN DEM JLC")
      )
      (libsource (lib "Eletro-mechanical") (part "Metal Screening Box - Top Cover"))
    )
    (comp (ref "R1")
      (value "100k")
      (footprint "RESC1005X40N")
      (description "Resistor - 1%")
      (fields
        (field (name "PART NUMBER") "R0402_100K_1%_0.0625W_100PPM")
        (field (name "POWER") "0.0625W")
        (field (name "AUTHOR") "CERN DEM JLC")
      )
      (libsource (lib "Resistors") (part "Resistor - 1%"))
    )
    (comp (ref "R2")
      (value "100k")
      (footprint "RESC1005X40N")
      (description "Resistor - 1%")
      (fields
        (field (name "PART NUMBER") "R0402_100K_1%_0.0625W_100PPM")
        (field (name "POWER") "0.0625W")
        (field (name "AUTHOR") "CERN DEM JLC")
      )
      (libsource (lib "Resistors") (part "Resistor - 1%"))
    )
    (comp (ref "R3")
      (value "200")
      (footprint "RESC1005X40N")
      (description "Resistor - 1%")
      (fields
        (field (name "PART NUMBER") "R0402_200R_1%_0.0625W_100PPM")
        (field (name "POWER") "0.0625W")
        (field (name "AUTHOR") "CERN DEM JLC")
      )
      (libsource (lib "Resistors") (part "Resistor - 1%"))
    )
    (comp (ref "R4")
      (value "200")
      (footprint "RESC1005X40N")
      (description "Resistor - 1%")
      (fields
        (field (name "PART NUMBER") "R0402_200R_1%_0.0625W_100PPM")
        (field (name "POWER") "0.0625W")
        (field (name "AUTHOR") "CERN DEM JLC")
      )
      (libsource (lib "Resistors") (part "Resistor - 1%"))
    )
    (comp (ref "R5")
      (value "200")
      (footprint "RESC1005X40N")
      (description "Resistor - 1%")
      (fields
        (field (name "PART NUMBER") "R0402_200R_1%_0.0625W_100PPM")
        (field (name "POWER") "0.0625W")
        (field (name "AUTHOR") "CERN DEM JLC")
      )
      (libsource (lib "Resistors") (part "Resistor - 1%"))
    )
    (comp (ref "R6")
      (value "1k2")
      (footprint "RESC1608X55N")
      (description "Resistor - 1%")
      (fields
        (field (name "PART NUMBER") "R0603_1K2_1%_0.1W_100PPM")
        (field (name "POWER") "0.1W")
        (field (name "AUTHOR") "CERN DEM JLC")
      )
      (libsource (lib "Resistors") (part "Resistor - 1%"))
    )
    (comp (ref "R7")
      (value "200")
      (footprint "RESC1005X40N")
      (description "Resistor - 1%")
      (fields
        (field (name "PART NUMBER") "R0402_200R_1%_0.0625W_100PPM")
        (field (name "POWER") "0.0625W")
        (field (name "AUTHOR") "CERN DEM JLC")
      )
      (libsource (lib "Resistors") (part "Resistor - 1%"))
    )
    (comp (ref "R8")
      (value "200")
      (footprint "RESC1005X40N")
      (description "Resistor - 1%")
      (fields
        (field (name "PART NUMBER") "R0402_200R_1%_0.0625W_100PPM")
        (field (name "POWER") "0.0625W")
        (field (name "AUTHOR") "CERN DEM JLC")
      )
      (libsource (lib "Resistors") (part "Resistor - 1%"))
    )
    (comp (ref "R9")
      (value "200")
      (footprint "RESC1005X40N")
      (description "Resistor - 1%")
      (fields
        (field (name "PART NUMBER") "R0402_200R_1%_0.0625W_100PPM")
        (field (name "POWER") "0.0625W")
        (field (name "AUTHOR") "CERN DEM JLC")
      )
      (libsource (lib "Resistors") (part "Resistor - 1%"))
    )
    (comp (ref "R10")
      (value "1k2")
      (footprint "RESC1608X55N")
      (description "Resistor - 1%")
      (fields
        (field (name "PART NUMBER") "R0603_1K2_1%_0.1W_100PPM")
        (field (name "POWER") "0.1W")
        (field (name "AUTHOR") "CERN DEM JLC")
      )
      (libsource (lib "Resistors") (part "Resistor - 1%"))
    )
    (comp (ref "R11")
      (value "200")
      (footprint "RESC1005X40N")
      (description "Resistor - 1%")
      (fields
        (field (name "PART NUMBER") "R0402_200R_1%_0.0625W_100PPM")
        (field (name "POWER") "0.0625W")
        (field (name "AUTHOR") "CERN DEM JLC")
      )
      (libsource (lib "Resistors") (part "Resistor - 1%"))
    )
    (comp (ref "R12")
      (value "200")
      (footprint "RESC1005X40N")
      (description "Resistor - 1%")
      (fields
        (field (name "PART NUMBER") "R0402_200R_1%_0.0625W_100PPM")
        (field (name "POWER") "0.0625W")
        (field (name "AUTHOR") "CERN DEM JLC")
      )
      (libsource (lib "Resistors") (part "Resistor - 1%"))
    )
    (comp (ref "R13")
      (value "1k2")
      (footprint "RESC1608X55N")
      (description "Resistor - 1%")
      (fields
        (field (name "PART NUMBER") "R0603_1K2_1%_0.1W_100PPM")
        (field (name "POWER") "0.1W")
        (field (name "AUTHOR") "CERN DEM JLC")
      )
      (libsource (lib "Resistors") (part "Resistor - 1%"))
    )
    (comp (ref "R14")
      (value "100k")
      (footprint "RESC1005X40N")
      (description "Resistor - 1%")
      (fields
        (field (name "PART NUMBER") "R0402_100K_1%_0.0625W_100PPM")
        (field (name "POWER") "0.0625W")
        (field (name "AUTHOR") "CERN DEM JLC")
      )
      (libsource (lib "Resistors") (part "Resistor - 1%"))
    )
    (comp (ref "R15")
      (value "200")
      (footprint "RESC1005X40N")
      (description "Resistor - 1%")
      (fields
        (field (name "PART NUMBER") "R0402_200R_1%_0.0625W_100PPM")
        (field (name "POWER") "0.0625W")
        (field (name "AUTHOR") "CERN DEM JLC")
      )
      (libsource (lib "Resistors") (part "Resistor - 1%"))
    )
    (comp (ref "R16")
      (value "1k2")
      (footprint "RESC1608X55N")
      (description "Resistor - 1%")
      (fields
        (field (name "PART NUMBER") "R0603_1K2_1%_0.1W_100PPM")
        (field (name "POWER") "0.1W")
        (field (name "AUTHOR") "CERN DEM JLC")
      )
      (libsource (lib "Resistors") (part "Resistor - 1%"))
    )
    (comp (ref "R17")
      (value "200")
      (footprint "RESC1005X40N")
      (description "Resistor - 1%")
      (fields
        (field (name "PART NUMBER") "R0402_200R_1%_0.0625W_100PPM")
        (field (name "POWER") "0.0625W")
        (field (name "AUTHOR") "CERN DEM JLC")
      )
      (libsource (lib "Resistors") (part "Resistor - 1%"))
    )
    (comp (ref "R18")
      (value "1k2")
      (footprint "RESC1608X55N")
      (description "Resistor - 1%")
      (fields
        (field (name "PART NUMBER") "R0603_1K2_1%_0.1W_100PPM")
        (field (name "POWER") "0.1W")
        (field (name "AUTHOR") "CERN DEM JLC")
      )
      (libsource (lib "Resistors") (part "Resistor - 1%"))
    )
    (comp (ref "R19")
      (value "200")
      (footprint "RESC1005X40N")
      (description "Resistor - 1%")
      (fields
        (field (name "PART NUMBER") "R0402_200R_1%_0.0625W_100PPM")
        (field (name "POWER") "0.0625W")
        (field (name "AUTHOR") "CERN DEM JLC")
      )
      (libsource (lib "Resistors") (part "Resistor - 1%"))
    )
    (comp (ref "R20")
      (value "200")
      (footprint "RESC1005X40N")
      (description "Resistor - 1%")
      (fields
        (field (name "PART NUMBER") "R0402_200R_1%_0.0625W_100PPM")
        (field (name "POWER") "0.0625W")
        (field (name "AUTHOR") "CERN DEM JLC")
      )
      (libsource (lib "Resistors") (part "Resistor - 1%"))
    )
    (comp (ref "R21")
      (value "100k")
      (footprint "RESC1005X40N")
      (description "Resistor - 1%")
      (fields
        (field (name "PART NUMBER") "R0402_100K_1%_0.0625W_100PPM")
        (field (name "POWER") "0.0625W")
        (field (name "AUTHOR") "CERN DEM JLC")
      )
      (libsource (lib "Resistors") (part "Resistor - 1%"))
    )
    (comp (ref "R22")
      (value "200")
      (footprint "RESC1005X40N")
      (description "Resistor - 1%")
      (fields
        (field (name "PART NUMBER") "R0402_200R_1%_0.0625W_100PPM")
        (field (name "POWER") "0.0625W")
        (field (name "AUTHOR") "CERN DEM JLC")
      )
      (libsource (lib "Resistors") (part "Resistor - 1%"))
    )
    (comp (ref "R23")
      (value "200")
      (footprint "RESC1005X40N")
      (description "Resistor - 1%")
      (fields
        (field (name "PART NUMBER") "R0402_200R_1%_0.0625W_100PPM")
        (field (name "POWER") "0.0625W")
        (field (name "AUTHOR") "CERN DEM JLC")
      )
      (libsource (lib "Resistors") (part "Resistor - 1%"))
    )
    (comp (ref "R24")
      (value "200")
      (footprint "RESC1005X40N")
      (description "Resistor - 1%")
      (fields
        (field (name "PART NUMBER") "R0402_200R_1%_0.0625W_100PPM")
        (field (name "POWER") "0.0625W")
        (field (name "AUTHOR") "CERN DEM JLC")
      )
      (libsource (lib "Resistors") (part "Resistor - 1%"))
    )
    (comp (ref "R25")
      (value "200")
      (footprint "RESC1005X40N")
      (description "Resistor - 1%")
      (fields
        (field (name "PART NUMBER") "R0402_200R_1%_0.0625W_100PPM")
        (field (name "POWER") "0.0625W")
        (field (name "AUTHOR") "CERN DEM JLC")
      )
      (libsource (lib "Resistors") (part "Resistor - 1%"))
    )
    (comp (ref "R26")
      (value "100k")
      (footprint "RESC1005X40N")
      (description "Resistor - 1%")
      (fields
        (field (name "PART NUMBER") "R0402_100K_1%_0.0625W_100PPM")
        (field (name "POWER") "0.0625W")
        (field (name "AUTHOR") "CERN DEM JLC")
      )
      (libsource (lib "Resistors") (part "Resistor - 1%"))
    )
    (comp (ref "R27")
      (value "200")
      (footprint "RESC1005X40N")
      (description "Resistor - 1%")
      (fields
        (field (name "PART NUMBER") "R0402_200R_1%_0.0625W_100PPM")
        (field (name "POWER") "0.0625W")
        (field (name "AUTHOR") "CERN DEM JLC")
      )
      (libsource (lib "Resistors") (part "Resistor - 1%"))
    )
    (comp (ref "R28")
      (value "200")
      (footprint "RESC1005X40N")
      (description "Resistor - 1%")
      (fields
        (field (name "PART NUMBER") "R0402_200R_1%_0.0625W_100PPM")
        (field (name "POWER") "0.0625W")
        (field (name "AUTHOR") "CERN DEM JLC")
      )
      (libsource (lib "Resistors") (part "Resistor - 1%"))
    )
    (comp (ref "R29")
      (value "200")
      (footprint "RESC1005X40N")
      (description "Resistor - 1%")
      (fields
        (field (name "PART NUMBER") "R0402_200R_1%_0.0625W_100PPM")
        (field (name "POWER") "0.0625W")
        (field (name "AUTHOR") "CERN DEM JLC")
      )
      (libsource (lib "Resistors") (part "Resistor - 1%"))
    )
    (comp (ref "R30")
      (value "100k")
      (footprint "RESC1005X40N")
      (description "Resistor - 1%")
      (fields
        (field (name "PART NUMBER") "R0402_100K_1%_0.0625W_100PPM")
        (field (name "POWER") "0.0625W")
        (field (name "AUTHOR") "CERN DEM JLC")
      )
      (libsource (lib "Resistors") (part "Resistor - 1%"))
    )
    (comp (ref "R31")
      (value "200")
      (footprint "RESC1005X40N")
      (description "Resistor - 1%")
      (fields
        (field (name "PART NUMBER") "R0402_200R_1%_0.0625W_100PPM")
        (field (name "POWER") "0.0625W")
        (field (name "AUTHOR") "CERN DEM JLC")
      )
      (libsource (lib "Resistors") (part "Resistor - 1%"))
    )
    (comp (ref "R32")
      (value "100k")
      (footprint "RESC1005X40N")
      (description "Resistor - 1%")
      (fields
        (field (name "PART NUMBER") "R0402_100K_1%_0.0625W_100PPM")
        (field (name "POWER") "0.0625W")
        (field (name "AUTHOR") "CERN DEM JLC")
      )
      (libsource (lib "Resistors") (part "Resistor - 1%"))
    )
    (comp (ref "R33")
      (value "100k")
      (footprint "RESC1005X40N")
      (description "Resistor - 1%")
      (fields
        (field (name "PART NUMBER") "R0402_100K_1%_0.0625W_100PPM")
        (field (name "POWER") "0.0625W")
        (field (name "AUTHOR") "CERN DEM JLC")
      )
      (libsource (lib "Resistors") (part "Resistor - 1%"))
    )
    (comp (ref "R34")
      (value "100k")
      (footprint "RESC1005X40N")
      (description "Resistor - 1%")
      (fields
        (field (name "PART NUMBER") "R0402_100K_1%_0.0625W_100PPM")
        (field (name "POWER") "0.0625W")
        (field (name "AUTHOR") "CERN DEM JLC")
      )
      (libsource (lib "Resistors") (part "Resistor - 1%"))
    )
    (comp (ref "R35")
      (value "12k")
      (footprint "RESC1608X55N")
      (description "Resistor - 1%")
      (fields
        (field (name "PART NUMBER") "R0603_12K_1%_0.1W_100PPM")
        (field (name "POWER") "0.1W")
        (field (name "AUTHOR") "CERN DEM JLC")
      )
      (libsource (lib "Resistors") (part "Resistor - 1%"))
    )
    (comp (ref "R36")
      (value "100k")
      (footprint "RESC1005X40N")
      (description "Resistor - 1%")
      (fields
        (field (name "PART NUMBER") "R0402_100K_1%_0.0625W_100PPM")
        (field (name "POWER") "0.0625W")
        (field (name "AUTHOR") "CERN DEM JLC")
      )
      (libsource (lib "Resistors") (part "Resistor - 1%"))
    )
    (comp (ref "R37")
      (value "100k")
      (footprint "RESC1005X40N")
      (description "Resistor - 1%")
      (fields
        (field (name "PART NUMBER") "R0402_100K_1%_0.0625W_100PPM")
        (field (name "POWER") "0.0625W")
        (field (name "AUTHOR") "CERN DEM JLC")
      )
      (libsource (lib "Resistors") (part "Resistor - 1%"))
    )
    (comp (ref "R38")
      (value "100k")
      (footprint "RESC1005X40N")
      (description "Resistor - 1%")
      (fields
        (field (name "PART NUMBER") "R0402_100K_1%_0.0625W_100PPM")
        (field (name "POWER") "0.0625W")
        (field (name "AUTHOR") "CERN DEM JLC")
      )
      (libsource (lib "Resistors") (part "Resistor - 1%"))
    )
    (comp (ref "R39")
      (value "3k3")
      (footprint "RESC1608X55N")
      (description "Resistor - 1%")
      (fields
        (field (name "PART NUMBER") "R0603_3K3_1%_0.1W_100PPM")
        (field (name "POWER") "0.1W")
        (field (name "AUTHOR") "CERN DEM JLC")
      )
      (libsource (lib "Resistors") (part "Resistor - 1%"))
    )
    (comp (ref "SW1")
      (value "Switch")
      (footprint "SW_TYCO_1-1437575-4")
      (description "SPDT Switch")
      (fields
        (field (name "PART NUMBER") "SW_TYCO_1-1437575-4")
        (field (name "MANUFACTURER") "TYCO")
        (field (name "AUTHOR") "CERN DEM JLC")
      )
      (libsource (lib "Eletro-mechanical") (part "SW SPDT 1NC-2C-3NO"))
    )
    (comp (ref "TP1")
      (value "Test Point")
      (footprint "TPS127")
      (fields (field (name "PART NUMBER") "SMD_PAD_1.27X1.27MM") (field (name "AUTHOR") "CERN DEM JLC"))
      (libsource (lib "Eletro-mechanical") (part "Test Point"))
    )
    (comp (ref "TP2")
      (value "Test Point")
      (footprint "TPS127")
      (fields (field (name "PART NUMBER") "SMD_PAD_1.27X1.27MM") (field (name "AUTHOR") "CERN DEM JLC"))
      (libsource (lib "Eletro-mechanical") (part "Test Point"))
    )
    (comp (ref "TR1")
      (value "1:2")
      (footprint "XFMR_MINI-CIRCUITS_DB1627")
      (description "50 OHMS 10 to 4000 MHz RF Transformer")
      (fields
        (field (name "PART NUMBER") "XFMR_MINI-CIRCUITS_TCM2-43X+")
        (field (name "POWER") "0.4W")
        (field (name "AUTHOR") "CERN DEM BC")
      )
      (libsource (lib "Inductors & Transformers") (part "XFMR_MINI-CIRCUITS_TCM2-43X"))
    )
    (comp (ref "TR2")
      (value "1:2")
      (footprint "XFMR_MINI-CIRCUITS_DB1627")
      (description "50 OHMS 10 to 4000 MHz RF Transformer")
      (fields
        (field (name "PART NUMBER") "XFMR_MINI-CIRCUITS_TCM2-43X+")
        (field (name "POWER") "0.4W")
        (field (name "AUTHOR") "CERN DEM BC")
      )
      (libsource (lib "") (part "XFMR_MINI-CIRCUITS_TCM2-43X_1"))
    )
    (comp (ref "TR3")
      (value "1:2")
      (footprint "XFMR_MINI-CIRCUITS_DB1627")
      (description "50 OHMS 10 to 4000 MHz RF Transformer")
      (fields
        (field (name "PART NUMBER") "XFMR_MINI-CIRCUITS_TCM2-43X+")
        (field (name "POWER") "0.4W")
        (field (name "AUTHOR") "CERN DEM BC")
      )
      (libsource (lib "Inductors & Transformers") (part "XFMR_MINI-CIRCUITS_TCM2-43X"))
    )
    (comp (ref "TR4")
      (value "1:2")
      (footprint "XFMR_MINI-CIRCUITS_DB1627")
      (description "50 OHMS 10 to 4000 MHz RF Transformer")
      (fields
        (field (name "PART NUMBER") "XFMR_MINI-CIRCUITS_TCM2-43X+")
        (field (name "POWER") "0.4W")
        (field (name "AUTHOR") "CERN DEM BC")
      )
      (libsource (lib "") (part "XFMR_MINI-CIRCUITS_TCM2-43X_1"))
    )
    (comp (ref "TR5")
      (value "1:2")
      (footprint "XFMR_MINI-CIRCUITS_DB1627")
      (description "50 OHMS 10 to 4000 MHz RF Transformer")
      (fields
        (field (name "PART NUMBER") "XFMR_MINI-CIRCUITS_TCM2-43X+")
        (field (name "POWER") "0.4W")
        (field (name "AUTHOR") "CERN DEM BC")
      )
      (libsource (lib "Inductors & Transformers") (part "XFMR_MINI-CIRCUITS_TCM2-43X"))
    )
    (comp (ref "TR6")
      (value "1:2")
      (footprint "XFMR_MINI-CIRCUITS_DB1627")
      (description "50 OHMS 10 to 4000 MHz RF Transformer")
      (fields
        (field (name "PART NUMBER") "XFMR_MINI-CIRCUITS_TCM2-43X+")
        (field (name "POWER") "0.4W")
        (field (name "AUTHOR") "CERN DEM BC")
      )
      (libsource (lib "Inductors & Transformers") (part "XFMR_MINI-CIRCUITS_TCM2-43X"))
    )
    (comp (ref "TR7")
      (value "1:2")
      (footprint "XFMR_MINI-CIRCUITS_DB1627")
      (description "50 OHMS 10 to 4000 MHz RF Transformer")
      (fields
        (field (name "PART NUMBER") "XFMR_MINI-CIRCUITS_TCM2-43X+")
        (field (name "POWER") "0.4W")
        (field (name "AUTHOR") "CERN DEM BC")
      )
      (libsource (lib "Inductors & Transformers") (part "XFMR_MINI-CIRCUITS_TCM2-43X"))
    )
    (comp (ref "TR8")
      (value "1:2")
      (footprint "XFMR_MINI-CIRCUITS_DB1627")
      (description "50 OHMS 10 to 4000 MHz RF Transformer")
      (fields
        (field (name "PART NUMBER") "XFMR_MINI-CIRCUITS_TCM2-43X+")
        (field (name "POWER") "0.4W")
        (field (name "AUTHOR") "CERN DEM BC")
      )
      (libsource (lib "Inductors & Transformers") (part "XFMR_MINI-CIRCUITS_TCM2-43X"))
    )
    (comp (ref "TR9")
      (value "1:2")
      (footprint "XFMR_MINI-CIRCUITS_DB1627")
      (description "50 OHMS 10 to 4000 MHz RF Transformer")
      (fields
        (field (name "PART NUMBER") "XFMR_MINI-CIRCUITS_TCM2-43X+")
        (field (name "POWER") "0.4W")
        (field (name "AUTHOR") "CERN DEM BC")
      )
      (libsource (lib "Inductors & Transformers") (part "XFMR_MINI-CIRCUITS_TCM2-43X"))
    )
    (comp (ref "TR10")
      (value "1:2")
      (footprint "XFMR_MINI-CIRCUITS_DB1627")
      (description "50 OHMS 10 to 4000 MHz RF Transformer")
      (fields
        (field (name "PART NUMBER") "XFMR_MINI-CIRCUITS_TCM2-43X+")
        (field (name "POWER") "0.4W")
        (field (name "AUTHOR") "CERN DEM BC")
      )
      (libsource (lib "Inductors & Transformers") (part "XFMR_MINI-CIRCUITS_TCM2-43X"))
    )
    (comp (ref "TR11")
      (value "1:2")
      (footprint "XFMR_MINI-CIRCUITS_DB1627")
      (description "50 OHMS 10 to 4000 MHz RF Transformer")
      (fields
        (field (name "PART NUMBER") "XFMR_MINI-CIRCUITS_TCM2-43X+")
        (field (name "POWER") "0.4W")
        (field (name "AUTHOR") "CERN DEM BC")
      )
      (libsource (lib "Inductors & Transformers") (part "XFMR_MINI-CIRCUITS_TCM2-43X"))
    )
    (comp (ref "TR12")
      (value "1:2")
      (footprint "XFMR_MINI-CIRCUITS_DB1627")
      (description "50 OHMS 10 to 4000 MHz RF Transformer")
      (fields
        (field (name "PART NUMBER") "XFMR_MINI-CIRCUITS_TCM2-43X+")
        (field (name "POWER") "0.4W")
        (field (name "AUTHOR") "CERN DEM BC")
      )
      (libsource (lib "Inductors & Transformers") (part "XFMR_MINI-CIRCUITS_TCM2-43X"))
    )
  )
  (nets
    (net (code "1") (name "/EEM_CLK_OUT0") (class "Default")
      (node (ref "C31") (pin "2") (pinfunction "2_2") (pintype "passive"))
      (node (ref "TR1") (pin "3") (pinfunction "P1_3") (pintype "passive"))
    )
    (net (code "2") (name "/EEM_CLK_OUT1") (class "Default")
      (node (ref "C38") (pin "2") (pinfunction "2_2") (pintype "passive"))
      (node (ref "TR3") (pin "3") (pinfunction "P1_3") (pintype "passive"))
    )
    (net (code "3") (name "/EEM_CLK_OUT2") (class "Default")
      (node (ref "C50") (pin "2") (pinfunction "2_2") (pintype "passive"))
      (node (ref "TR5") (pin "3") (pinfunction "P1_3") (pintype "passive"))
    )
    (net (code "4") (name "/EEM_CLK_OUT3") (class "Default")
      (node (ref "C55") (pin "2") (pinfunction "2_2") (pintype "passive"))
      (node (ref "TR6") (pin "3") (pinfunction "P1_3") (pintype "passive"))
    )
    (net (code "5") (name "/EEM_CLK_OUT4") (class "Default")
      (node (ref "C60") (pin "2") (pinfunction "2_2") (pintype "passive"))
      (node (ref "TR7") (pin "3") (pinfunction "P1_3") (pintype "passive"))
    )
    (net (code "6") (name "/EEM_CLK_OUT5") (class "Default")
      (node (ref "C67") (pin "2") (pinfunction "2_2") (pintype "passive"))
      (node (ref "TR8") (pin "3") (pinfunction "P1_3") (pintype "passive"))
    )
    (net (code "7") (name "/EEM_CLK_OUT6") (class "Default")
      (node (ref "C76") (pin "2") (pinfunction "2_2") (pintype "passive"))
      (node (ref "TR9") (pin "3") (pinfunction "P1_3") (pintype "passive"))
    )
    (net (code "8") (name "/EEM_CLK_OUT7") (class "Default")
      (node (ref "C82") (pin "2") (pinfunction "2_2") (pintype "passive"))
      (node (ref "TR10") (pin "3") (pinfunction "P1_3") (pintype "passive"))
    )
    (net (code "9") (name "/EEM_CLK_OUT8") (class "Default")
      (node (ref "C91") (pin "2") (pinfunction "2_2") (pintype "passive"))
      (node (ref "TR11") (pin "3") (pinfunction "P1_3") (pintype "passive"))
    )
    (net (code "10") (name "/EEM_CLK_OUT9") (class "Default")
      (node (ref "C97") (pin "2") (pinfunction "2_2") (pintype "passive"))
      (node (ref "TR12") (pin "3") (pinfunction "P1_3") (pintype "passive"))
    )
    (net (code "11") (name "/EEM_OUT0_N") (class "Default")
      (node (ref "C11") (pin "2") (pinfunction "2_2") (pintype "passive"))
      (node (ref "IC1") (pin "12") (pinfunction "~{Q9}_12") (pintype "output"))
      (node (ref "R31") (pin "1") (pinfunction "1_1") (pintype "passive"))
    )
    (net (code "12") (name "/EEM_OUT0_P") (class "Default")
      (node (ref "C18") (pin "2") (pinfunction "2_2") (pintype "passive"))
      (node (ref "IC1") (pin "13") (pinfunction "Q9_13") (pintype "output"))
      (node (ref "R29") (pin "1") (pinfunction "1_1") (pintype "passive"))
    )
    (net (code "13") (name "/EEM_OUT1_N") (class "Default")
      (node (ref "C20") (pin "2") (pinfunction "2_2") (pintype "passive"))
      (node (ref "IC1") (pin "14") (pinfunction "~{Q8}_14") (pintype "output"))
      (node (ref "R28") (pin "1") (pinfunction "1_1") (pintype "passive"))
    )
    (net (code "14") (name "/EEM_OUT1_P") (class "Default")
      (node (ref "C22") (pin "2") (pinfunction "2_2") (pintype "passive"))
      (node (ref "IC1") (pin "15") (pinfunction "Q8_15") (pintype "output"))
      (node (ref "R27") (pin "1") (pinfunction "1_1") (pintype "passive"))
    )
    (net (code "15") (name "/EEM_OUT2_N") (class "Default")
      (node (ref "C25") (pin "2") (pinfunction "2_2") (pintype "passive"))
      (node (ref "IC1") (pin "16") (pinfunction "~{Q7}_16") (pintype "output"))
      (node (ref "R25") (pin "1") (pinfunction "1_1") (pintype "passive"))
    )
    (net (code "16") (name "/EEM_OUT2_P") (class "Default")
      (node (ref "C29") (pin "2") (pinfunction "2_2") (pintype "passive"))
      (node (ref "IC1") (pin "17") (pinfunction "Q7_17") (pintype "output"))
      (node (ref "R24") (pin "1") (pinfunction "1_1") (pintype "passive"))
    )
    (net (code "17") (name "/EEM_OUT3_N") (class "Default")
      (node (ref "C34") (pin "2") (pinfunction "2_2") (pintype "passive"))
      (node (ref "IC1") (pin "18") (pinfunction "~{Q6}_18") (pintype "output"))
      (node (ref "R23") (pin "1") (pinfunction "1_1") (pintype "passive"))
    )
    (net (code "18") (name "/EEM_OUT3_P") (class "Default")
      (node (ref "C37") (pin "2") (pinfunction "2_2") (pintype "passive"))
      (node (ref "IC1") (pin "19") (pinfunction "Q6_19") (pintype "output"))
      (node (ref "R22") (pin "1") (pinfunction "1_1") (pintype "passive"))
    )
    (net (code "19") (name "/EEM_OUT4_N") (class "Default")
      (node (ref "C41") (pin "2") (pinfunction "2_2") (pintype "passive"))
      (node (ref "IC1") (pin "24") (pinfunction "~{Q5}_24") (pintype "output"))
      (node (ref "R20") (pin "1") (pinfunction "1_1") (pintype "passive"))
    )
    (net (code "20") (name "/EEM_OUT4_P") (class "Default")
      (node (ref "C51") (pin "2") (pinfunction "2_2") (pintype "passive"))
      (node (ref "IC1") (pin "25") (pinfunction "Q5_25") (pintype "output"))
      (node (ref "R19") (pin "1") (pinfunction "1_1") (pintype "passive"))
    )
    (net (code "21") (name "/EEM_OUT5_N") (class "Default")
      (node (ref "C54") (pin "2") (pinfunction "2_2") (pintype "passive"))
      (node (ref "IC1") (pin "26") (pinfunction "~{Q4}_26") (pintype "output"))
      (node (ref "R17") (pin "1") (pinfunction "1_1") (pintype "passive"))
    )
    (net (code "22") (name "/EEM_OUT5_P") (class "Default")
      (node (ref "C59") (pin "2") (pinfunction "2_2") (pintype "passive"))
      (node (ref "IC1") (pin "27") (pinfunction "Q4_27") (pintype "output"))
      (node (ref "R15") (pin "1") (pinfunction "1_1") (pintype "passive"))
    )
    (net (code "23") (name "/EEM_OUT6_N") (class "Default")
      (node (ref "C63") (pin "2") (pinfunction "2_2") (pintype "passive"))
      (node (ref "IC1") (pin "32") (pinfunction "~{Q3}_32") (pintype "output"))
      (node (ref "R12") (pin "1") (pinfunction "1_1") (pintype "passive"))
    )
    (net (code "24") (name "/EEM_OUT6_P") (class "Default")
      (node (ref "C66") (pin "2") (pinfunction "2_2") (pintype "passive"))
      (node (ref "IC1") (pin "33") (pinfunction "Q3_33") (pintype "output"))
      (node (ref "R11") (pin "1") (pinfunction "1_1") (pintype "passive"))
    )
    (net (code "25") (name "/EEM_OUT7_N") (class "Default")
      (node (ref "C74") (pin "2") (pinfunction "2_2") (pintype "passive"))
      (node (ref "IC1") (pin "34") (pinfunction "~{Q2}_34") (pintype "output"))
      (node (ref "R9") (pin "1") (pinfunction "1_1") (pintype "passive"))
    )
    (net (code "26") (name "/EEM_OUT7_P") (class "Default")
      (node (ref "C78") (pin "2") (pinfunction "2_2") (pintype "passive"))
      (node (ref "IC1") (pin "35") (pinfunction "Q2_35") (pintype "output"))
      (node (ref "R8") (pin "1") (pinfunction "1_1") (pintype "passive"))
    )
    (net (code "27") (name "/EEM_OUT8_N") (class "Default")
      (node (ref "C84") (pin "2") (pinfunction "2_2") (pintype "passive"))
      (node (ref "IC1") (pin "36") (pinfunction "~{Q1}_36") (pintype "output"))
      (node (ref "R7") (pin "1") (pinfunction "1_1") (pintype "passive"))
    )
    (net (code "28") (name "/EEM_OUT8_P") (class "Default")
      (node (ref "C90") (pin "2") (pinfunction "2_2") (pintype "passive"))
      (node (ref "IC1") (pin "37") (pinfunction "Q1_37") (pintype "output"))
      (node (ref "R5") (pin "1") (pinfunction "1_1") (pintype "passive"))
    )
    (net (code "29") (name "/EEM_OUT9_N") (class "Default")
      (node (ref "C94") (pin "2") (pinfunction "2_2") (pintype "passive"))
      (node (ref "IC1") (pin "38") (pinfunction "~{Q0}_38") (pintype "output"))
      (node (ref "R4") (pin "1") (pinfunction "1_1") (pintype "passive"))
    )
    (net (code "30") (name "/EEM_OUT9_P") (class "Default")
      (node (ref "C98") (pin "2") (pinfunction "2_2") (pintype "passive"))
      (node (ref "IC1") (pin "39") (pinfunction "Q0_39") (pintype "output"))
      (node (ref "R3") (pin "1") (pinfunction "1_1") (pintype "passive"))
    )
    (net (code "31") (name "/GND0") (class "Default")
      (node (ref "C26") (pin "1") (pinfunction "1_1") (pintype "passive"))
      (node (ref "C30") (pin "2") (pinfunction "2_2") (pintype "passive"))
      (node (ref "J3") (pin "2") (pinfunction "2_2") (pintype "bidirectional"))
      (node (ref "R14") (pin "2") (pinfunction "2_2") (pintype "passive"))
    )
    (net (code "32") (name "/GND1") (class "Default")
      (node (ref "C33") (pin "1") (pinfunction "1_1") (pintype "passive"))
      (node (ref "C36") (pin "2") (pinfunction "2_2") (pintype "passive"))
      (node (ref "J4") (pin "2") (pinfunction "2_2") (pintype "bidirectional"))
      (node (ref "R21") (pin "2") (pinfunction "2_2") (pintype "passive"))
    )
    (net (code "33") (name "/GND2") (class "Default")
      (node (ref "C39") (pin "1") (pinfunction "1_1") (pintype "passive"))
      (node (ref "C47") (pin "2") (pinfunction "2_2") (pintype "passive"))
      (node (ref "J5") (pin "2") (pinfunction "2_2") (pintype "bidirectional"))
      (node (ref "R26") (pin "2") (pinfunction "2_2") (pintype "passive"))
    )
    (net (code "34") (name "/GND3") (class "Default")
      (node (ref "C49") (pin "1") (pinfunction "1_1") (pintype "passive"))
      (node (ref "C52") (pin "2") (pinfunction "2_2") (pintype "passive"))
      (node (ref "J6") (pin "2") (pinfunction "2_2") (pintype "bidirectional"))
      (node (ref "R30") (pin "2") (pinfunction "2_2") (pintype "passive"))
    )
    (net (code "35") (name "/GND4") (class "Default")
      (node (ref "C56") (pin "1") (pinfunction "1_1") (pintype "passive"))
      (node (ref "C58") (pin "2") (pinfunction "2_2") (pintype "passive"))
      (node (ref "J7") (pin "2") (pinfunction "2_2") (pintype "bidirectional"))
      (node (ref "R32") (pin "2") (pinfunction "2_2") (pintype "passive"))
    )
    (net (code "36") (name "/GND5") (class "Default")
      (node (ref "C61") (pin "1") (pinfunction "1_1") (pintype "passive"))
      (node (ref "C64") (pin "2") (pinfunction "2_2") (pintype "passive"))
      (node (ref "J8") (pin "2") (pinfunction "2_2") (pintype "bidirectional"))
      (node (ref "R33") (pin "2") (pinfunction "2_2") (pintype "passive"))
    )
    (net (code "37") (name "/GND6") (class "Default")
      (node (ref "C68") (pin "1") (pinfunction "1_1") (pintype "passive"))
      (node (ref "C73") (pin "2") (pinfunction "2_2") (pintype "passive"))
      (node (ref "J9") (pin "2") (pinfunction "2_2") (pintype "bidirectional"))
      (node (ref "R34") (pin "2") (pinfunction "2_2") (pintype "passive"))
    )
    (net (code "38") (name "/GND7") (class "Default")
      (node (ref "C75") (pin "1") (pinfunction "1_1") (pintype "passive"))
      (node (ref "C79") (pin "2") (pinfunction "2_2") (pintype "passive"))
      (node (ref "J11") (pin "2") (pinfunction "2_2") (pintype "bidirectional"))
      (node (ref "R36") (pin "2") (pinfunction "2_2") (pintype "passive"))
    )
    (net (code "39") (name "/GND8") (class "Default")
      (node (ref "C83") (pin "1") (pinfunction "1_1") (pintype "passive"))
      (node (ref "C89") (pin "2") (pinfunction "2_2") (pintype "passive"))
      (node (ref "J13") (pin "2") (pinfunction "2_2") (pintype "bidirectional"))
      (node (ref "R37") (pin "2") (pinfunction "2_2") (pintype "passive"))
    )
    (net (code "40") (name "/GND9") (class "Default")
      (node (ref "C92") (pin "1") (pinfunction "1_1") (pintype "passive"))
      (node (ref "C95") (pin "2") (pinfunction "2_2") (pintype "passive"))
      (node (ref "J14") (pin "2") (pinfunction "2_2") (pintype "bidirectional"))
      (node (ref "R38") (pin "2") (pinfunction "2_2") (pintype "passive"))
    )
    (net (code "41") (name "/GND10") (class "Default")
      (node (ref "C4") (pin "1") (pinfunction "1_1") (pintype "passive"))
      (node (ref "C7") (pin "1") (pinfunction "1_1") (pintype "passive"))
      (node (ref "J1") (pin "2") (pinfunction "2_2") (pintype "bidirectional"))
      (node (ref "R1") (pin "2") (pinfunction "2_2") (pintype "passive"))
    )
    (net (code "42") (name "/GND11") (class "Default")
      (node (ref "C13") (pin "1") (pinfunction "1_1") (pintype "passive"))
      (node (ref "C17") (pin "1") (pinfunction "1_1") (pintype "passive"))
      (node (ref "J2") (pin "2") (pinfunction "2_2") (pintype "bidirectional"))
      (node (ref "R2") (pin "2") (pinfunction "2_2") (pintype "passive"))
    )
    (net (code "43") (name "/IN_CLK0_N") (class "Default")
      (node (ref "C9") (pin "2") (pinfunction "2_2") (pintype "passive"))
      (node (ref "IC1") (pin "3") (pinfunction "~{CLK0}_3") (pintype "input"))
    )
    (net (code "44") (name "/IN_CLK0_P") (class "Default")
      (node (ref "C15") (pin "2") (pinfunction "2_2") (pintype "passive"))
      (node (ref "IC1") (pin "2") (pinfunction "CLK0_2") (pintype "input"))
    )
    (net (code "45") (name "/IN_CLK1_N") (class "Default")
      (node (ref "C2") (pin "2") (pinfunction "2_2") (pintype "passive"))
      (node (ref "IC1") (pin "7") (pinfunction "~{CLK1}_7") (pintype "input"))
    )
    (net (code "46") (name "/IN_CLK1_P") (class "Default")
      (node (ref "C5") (pin "2") (pinfunction "2_2") (pintype "passive"))
      (node (ref "IC1") (pin "6") (pinfunction "CLK1_6") (pintype "input"))
    )
    (net (code "47") (name "/PGOOD") (class "Default")
      (node (ref "IC2") (pin "C2") (pinfunction "PGOOD_C2") (pintype "open_collector"))
      (node (ref "IC3") (pin "4") (pinfunction "PG_4") (pintype "output"))
      (node (ref "LD1") (pin "2") (pinfunction "A_2") (pintype "passive"))
      (node (ref "R16") (pin "1") (pinfunction "1_1") (pintype "passive"))
      (node (ref "R18") (pin "1") (pinfunction "1_1") (pintype "passive"))
    )
    (net (code "48") (name "GND") (class "Default")
      (node (ref "B1") (pin "1") (pinfunction "1_1") (pintype "bidirectional"))
      (node (ref "B2") (pin "1") (pinfunction "1_1") (pintype "bidirectional"))
      (node (ref "B3") (pin "1") (pinfunction "1_1") (pintype "bidirectional"))
      (node (ref "C10") (pin "2") (pinfunction "2_2") (pintype "passive"))
      (node (ref "C100") (pin "1") (pinfunction "1_1") (pintype "passive"))
      (node (ref "C101") (pin "2") (pinfunction "2_2") (pintype "passive"))
      (node (ref "C12") (pin "1") (pinfunction "1_1") (pintype "passive"))
      (node (ref "C13") (pin "2") (pinfunction "2_2") (pintype "passive"))
      (node (ref "C14") (pin "1") (pinfunction "1_1") (pintype "passive"))
      (node (ref "C16") (pin "2") (pinfunction "2_2") (pintype "passive"))
      (node (ref "C17") (pin "2") (pinfunction "2_2") (pintype "passive"))
      (node (ref "C19") (pin "2") (pinfunction "2_2") (pintype "passive"))
      (node (ref "C21") (pin "1") (pinfunction "1_1") (pintype "passive"))
      (node (ref "C23") (pin "1") (pinfunction "1_1") (pintype "passive"))
      (node (ref "C24") (pin "2") (pinfunction "2_2") (pintype "passive"))
      (node (ref "C26") (pin "2") (pinfunction "2_2") (pintype "passive"))
      (node (ref "C27") (pin "1") (pinfunction "1_1") (pintype "passive"))
      (node (ref "C28") (pin "1") (pinfunction "1_1") (pintype "passive"))
      (node (ref "C3") (pin "1") (pinfunction "1_1") (pintype "passive"))
      (node (ref "C30") (pin "1") (pinfunction "1_1") (pintype "passive"))
      (node (ref "C32") (pin "2") (pinfunction "2_2") (pintype "passive"))
      (node (ref "C33") (pin "2") (pinfunction "2_2") (pintype "passive"))
      (node (ref "C35") (pin "1") (pinfunction "1_1") (pintype "passive"))
      (node (ref "C36") (pin "1") (pinfunction "1_1") (pintype "passive"))
      (node (ref "C39") (pin "2") (pinfunction "2_2") (pintype "passive"))
      (node (ref "C4") (pin "2") (pinfunction "2_2") (pintype "passive"))
      (node (ref "C40") (pin "2") (pinfunction "2_2") (pintype "passive"))
      (node (ref "C42") (pin "1") (pinfunction "1_1") (pintype "passive"))
      (node (ref "C43") (pin "1") (pinfunction "1_1") (pintype "passive"))
      (node (ref "C44") (pin "1") (pinfunction "1_1") (pintype "passive"))
      (node (ref "C45") (pin "1") (pinfunction "1_1") (pintype "passive"))
      (node (ref "C46") (pin "1") (pinfunction "1_1") (pintype "passive"))
      (node (ref "C47") (pin "1") (pinfunction "1_1") (pintype "passive"))
      (node (ref "C48") (pin "1") (pinfunction "1_1") (pintype "passive"))
      (node (ref "C49") (pin "2") (pinfunction "2_2") (pintype "passive"))
      (node (ref "C52") (pin "1") (pinfunction "1_1") (pintype "passive"))
      (node (ref "C53") (pin "2") (pinfunction "2_2") (pintype "passive"))
      (node (ref "C56") (pin "2") (pinfunction "2_2") (pintype "passive"))
      (node (ref "C57") (pin "1") (pinfunction "1_1") (pintype "passive"))
      (node (ref "C58") (pin "1") (pinfunction "1_1") (pintype "passive"))
      (node (ref "C6") (pin "2") (pinfunction "2_2") (pintype "passive"))
      (node (ref "C61") (pin "2") (pinfunction "2_2") (pintype "passive"))
      (node (ref "C62") (pin "2") (pinfunction "2_2") (pintype "passive"))
      (node (ref "C64") (pin "1") (pinfunction "1_1") (pintype "passive"))
      (node (ref "C65") (pin "1") (pinfunction "1_1") (pintype "passive"))
      (node (ref "C68") (pin "2") (pinfunction "2_2") (pintype "passive"))
      (node (ref "C69") (pin "1") (pinfunction "1_1") (pintype "passive"))
      (node (ref "C7") (pin "2") (pinfunction "2_2") (pintype "passive"))
      (node (ref "C70") (pin "1") (pinfunction "1_1") (pintype "passive"))
      (node (ref "C71") (pin "1") (pinfunction "1_1") (pintype "passive"))
      (node (ref "C72") (pin "2") (pinfunction "2_2") (pintype "passive"))
      (node (ref "C73") (pin "1") (pinfunction "1_1") (pintype "passive"))
      (node (ref "C75") (pin "2") (pinfunction "2_2") (pintype "passive"))
      (node (ref "C77") (pin "1") (pinfunction "1_1") (pintype "passive"))
      (node (ref "C79") (pin "1") (pinfunction "1_1") (pintype "passive"))
      (node (ref "C80") (pin "1") (pinfunction "1_1") (pintype "passive"))
      (node (ref "C81") (pin "2") (pinfunction "2_2") (pintype "passive"))
      (node (ref "C83") (pin "2") (pinfunction "2_2") (pintype "passive"))
      (node (ref "C85") (pin "2") (pinfunction "2_2") (pintype "passive"))
      (node (ref "C86") (pin "1") (pinfunction "1_1") (pintype "passive"))
      (node (ref "C87") (pin "2") (pinfunction "2_2") (pintype "passive"))
      (node (ref "C88") (pin "1") (pinfunction "1_1") (pintype "passive"))
      (node (ref "C89") (pin "1") (pinfunction "1_1") (pintype "passive"))
      (node (ref "C92") (pin "2") (pinfunction "2_2") (pintype "passive"))
      (node (ref "C93") (pin "2") (pinfunction "2_2") (pintype "passive"))
      (node (ref "C95") (pin "1") (pinfunction "1_1") (pintype "passive"))
      (node (ref "C96") (pin "1") (pinfunction "1_1") (pintype "passive"))
      (node (ref "C99") (pin "2") (pinfunction "2_2") (pintype "passive"))
      (node (ref "D1") (pin "2") (pinfunction "A_2") (pintype "passive"))
      (node (ref "FL1") (pin "4") (pinfunction "CG_4") (pintype "passive"))
      (node (ref "IC1") (pin "10") (pinfunction "VEE_10") (pintype "power_in"))
      (node (ref "IC1") (pin "41") (pinfunction "EP_41") (pintype "power_in"))
      (node (ref "IC2") (pin "B3") (pinfunction "GND_B3") (pintype "power_in"))
      (node (ref "IC2") (pin "B4") (pinfunction "SGND_B4") (pintype "power_in"))
      (node (ref "IC2") (pin "C3") (pinfunction "GND_C3") (pintype "power_in"))
      (node (ref "IC2") (pin "D3") (pinfunction "GND_D3") (pintype "power_in"))
      (node (ref "IC2") (pin "D4") (pinfunction "GND_D4") (pintype "power_in"))
      (node (ref "IC2") (pin "E3") (pinfunction "GND_E3") (pintype "power_in"))
      (node (ref "IC3") (pin "11") (pinfunction "GND_11") (pintype "power_in"))
      (node (ref "IC3") (pin "5") (pinfunction "ILIM_5") (pintype "input"))
      (node (ref "IC3") (pin "8") (pinfunction "GND_8") (pintype "power_in"))
      (node (ref "J10") (pin "1") (pinfunction "1_1") (pintype "bidirectional"))
      (node (ref "J10") (pin "10") (pinfunction "10_10") (pintype "bidirectional"))
      (node (ref "J10") (pin "13") (pinfunction "13_13") (pintype "bidirectional"))
      (node (ref "J10") (pin "16") (pinfunction "16_16") (pintype "bidirectional"))
      (node (ref "J10") (pin "19") (pinfunction "19_19") (pintype "bidirectional"))
      (node (ref "J10") (pin "22") (pinfunction "22_22") (pintype "bidirectional"))
      (node (ref "J10") (pin "25") (pinfunction "25_25") (pintype "bidirectional"))
      (node (ref "J10") (pin "4") (pinfunction "4_4") (pintype "bidirectional"))
      (node (ref "J10") (pin "7") (pinfunction "7_7") (pintype "bidirectional"))
      (node (ref "LD1") (pin "1") (pinfunction "C_1") (pintype "passive"))
      (node (ref "LD1") (pin "3") (pinfunction "C_3") (pintype "passive"))
      (node (ref "MSBOX1") (pin "1") (pinfunction "1_1") (pintype "passive"))
      (node (ref "MSBOX1") (pin "10") (pinfunction "10_10") (pintype "passive"))
      (node (ref "MSBOX1") (pin "11") (pinfunction "11_11") (pintype "passive"))
      (node (ref "MSBOX1") (pin "12") (pinfunction "12_12") (pintype "passive"))
      (node (ref "MSBOX1") (pin "13") (pinfunction "13_13") (pintype "passive"))
      (node (ref "MSBOX1") (pin "14") (pinfunction "14_14") (pintype "passive"))
      (node (ref "MSBOX1") (pin "15") (pinfunction "15_15") (pintype "passive"))
      (node (ref "MSBOX1") (pin "16") (pinfunction "16_16") (pintype "passive"))
      (node (ref "MSBOX1") (pin "17") (pinfunction "17_17") (pintype "passive"))
      (node (ref "MSBOX1") (pin "18") (pinfunction "18_18") (pintype "passive"))
      (node (ref "MSBOX1") (pin "19") (pinfunction "19_19") (pintype "passive"))
      (node (ref "MSBOX1") (pin "2") (pinfunction "2_2") (pintype "passive"))
      (node (ref "MSBOX1") (pin "20") (pinfunction "20_20") (pintype "passive"))
      (node (ref "MSBOX1") (pin "21") (pinfunction "21_21") (pintype "passive"))
      (node (ref "MSBOX1") (pin "22") (pinfunction "22_22") (pintype "passive"))
      (node (ref "MSBOX1") (pin "23") (pinfunction "23_23") (pintype "passive"))
      (node (ref "MSBOX1") (pin "24") (pinfunction "24_24") (pintype "passive"))
      (node (ref "MSBOX1") (pin "25") (pinfunction "25_25") (pintype "passive"))
      (node (ref "MSBOX1") (pin "26") (pinfunction "26_26") (pintype "passive"))
      (node (ref "MSBOX1") (pin "27") (pinfunction "27_27") (pintype "passive"))
      (node (ref "MSBOX1") (pin "28") (pinfunction "28_28") (pintype "passive"))
      (node (ref "MSBOX1") (pin "3") (pinfunction "3_3") (pintype "passive"))
      (node (ref "MSBOX1") (pin "4") (pinfunction "4_4") (pintype "passive"))
      (node (ref "MSBOX1") (pin "5") (pinfunction "5_5") (pintype "passive"))
      (node (ref "MSBOX1") (pin "6") (pinfunction "6_6") (pintype "passive"))
      (node (ref "MSBOX1") (pin "7") (pinfunction "7_7") (pintype "passive"))
      (node (ref "MSBOX1") (pin "8") (pinfunction "8_8") (pintype "passive"))
      (node (ref "MSBOX1") (pin "9") (pinfunction "9_9") (pintype "passive"))
      (node (ref "R1") (pin "1") (pinfunction "1_1") (pintype "passive"))
      (node (ref "R11") (pin "2") (pinfunction "2_2") (pintype "passive"))
      (node (ref "R12") (pin "2") (pinfunction "2_2") (pintype "passive"))
      (node (ref "R14") (pin "1") (pinfunction "1_1") (pintype "passive"))
      (node (ref "R15") (pin "2") (pinfunction "2_2") (pintype "passive"))
      (node (ref "R17") (pin "2") (pinfunction "2_2") (pintype "passive"))
      (node (ref "R19") (pin "2") (pinfunction "2_2") (pintype "passive"))
      (node (ref "R2") (pin "1") (pinfunction "1_1") (pintype "passive"))
      (node (ref "R20") (pin "2") (pinfunction "2_2") (pintype "passive"))
      (node (ref "R21") (pin "1") (pinfunction "1_1") (pintype "passive"))
      (node (ref "R22") (pin "2") (pinfunction "2_2") (pintype "passive"))
      (node (ref "R23") (pin "2") (pinfunction "2_2") (pintype "passive"))
      (node (ref "R24") (pin "2") (pinfunction "2_2") (pintype "passive"))
      (node (ref "R25") (pin "2") (pinfunction "2_2") (pintype "passive"))
      (node (ref "R26") (pin "1") (pinfunction "1_1") (pintype "passive"))
      (node (ref "R27") (pin "2") (pinfunction "2_2") (pintype "passive"))
      (node (ref "R28") (pin "2") (pinfunction "2_2") (pintype "passive"))
      (node (ref "R29") (pin "2") (pinfunction "2_2") (pintype "passive"))
      (node (ref "R3") (pin "2") (pinfunction "2_2") (pintype "passive"))
      (node (ref "R30") (pin "1") (pinfunction "1_1") (pintype "passive"))
      (node (ref "R31") (pin "2") (pinfunction "2_2") (pintype "passive"))
      (node (ref "R32") (pin "1") (pinfunction "1_1") (pintype "passive"))
      (node (ref "R33") (pin "1") (pinfunction "1_1") (pintype "passive"))
      (node (ref "R34") (pin "1") (pinfunction "1_1") (pintype "passive"))
      (node (ref "R35") (pin "2") (pinfunction "2_2") (pintype "passive"))
      (node (ref "R36") (pin "1") (pinfunction "1_1") (pintype "passive"))
      (node (ref "R37") (pin "1") (pinfunction "1_1") (pintype "passive"))
      (node (ref "R38") (pin "1") (pinfunction "1_1") (pintype "passive"))
      (node (ref "R39") (pin "2") (pinfunction "2_2") (pintype "passive"))
      (node (ref "R4") (pin "2") (pinfunction "2_2") (pintype "passive"))
      (node (ref "R5") (pin "2") (pinfunction "2_2") (pintype "passive"))
      (node (ref "R6") (pin "2") (pinfunction "2_2") (pintype "passive"))
      (node (ref "R7") (pin "2") (pinfunction "2_2") (pintype "passive"))
      (node (ref "R8") (pin "2") (pinfunction "2_2") (pintype "passive"))
      (node (ref "R9") (pin "2") (pinfunction "2_2") (pintype "passive"))
      (node (ref "TR1") (pin "1") (pinfunction "P1_1") (pintype "passive"))
      (node (ref "TR1") (pin "2") (pinfunction "P1_2") (pintype "passive"))
      (node (ref "TR1") (pin "5") (pinfunction "NC_5") (pintype "passive"))
      (node (ref "TR10") (pin "1") (pinfunction "P1_1") (pintype "passive"))
      (node (ref "TR10") (pin "2") (pinfunction "P1_2") (pintype "passive"))
      (node (ref "TR10") (pin "5") (pinfunction "NC_5") (pintype "passive"))
      (node (ref "TR11") (pin "1") (pinfunction "P1_1") (pintype "passive"))
      (node (ref "TR11") (pin "2") (pinfunction "P1_2") (pintype "passive"))
      (node (ref "TR11") (pin "5") (pinfunction "NC_5") (pintype "passive"))
      (node (ref "TR12") (pin "1") (pinfunction "P1_1") (pintype "passive"))
      (node (ref "TR12") (pin "2") (pinfunction "P1_2") (pintype "passive"))
      (node (ref "TR12") (pin "5") (pinfunction "NC_5") (pintype "passive"))
      (node (ref "TR2") (pin "1") (pinfunction "P1_1") (pintype "passive"))
      (node (ref "TR2") (pin "2") (pinfunction "P1_2") (pintype "passive"))
      (node (ref "TR2") (pin "5") (pinfunction "NC_5") (pintype "passive"))
      (node (ref "TR3") (pin "1") (pinfunction "P1_1") (pintype "passive"))
      (node (ref "TR3") (pin "2") (pinfunction "P1_2") (pintype "passive"))
      (node (ref "TR3") (pin "5") (pinfunction "NC_5") (pintype "passive"))
      (node (ref "TR4") (pin "1") (pinfunction "P1_1") (pintype "passive"))
      (node (ref "TR4") (pin "2") (pinfunction "P1_2") (pintype "passive"))
      (node (ref "TR4") (pin "5") (pinfunction "NC_5") (pintype "passive"))
      (node (ref "TR5") (pin "1") (pinfunction "P1_1") (pintype "passive"))
      (node (ref "TR5") (pin "2") (pinfunction "P1_2") (pintype "passive"))
      (node (ref "TR5") (pin "5") (pinfunction "NC_5") (pintype "passive"))
      (node (ref "TR6") (pin "1") (pinfunction "P1_1") (pintype "passive"))
      (node (ref "TR6") (pin "2") (pinfunction "P1_2") (pintype "passive"))
      (node (ref "TR6") (pin "5") (pinfunction "NC_5") (pintype "passive"))
      (node (ref "TR7") (pin "1") (pinfunction "P1_1") (pintype "passive"))
      (node (ref "TR7") (pin "2") (pinfunction "P1_2") (pintype "passive"))
      (node (ref "TR7") (pin "5") (pinfunction "NC_5") (pintype "passive"))
      (node (ref "TR8") (pin "1") (pinfunction "P1_1") (pintype "passive"))
      (node (ref "TR8") (pin "2") (pinfunction "P1_2") (pintype "passive"))
      (node (ref "TR8") (pin "5") (pinfunction "NC_5") (pintype "passive"))
      (node (ref "TR9") (pin "1") (pinfunction "P1_1") (pintype "passive"))
      (node (ref "TR9") (pin "2") (pinfunction "P1_2") (pintype "passive"))
      (node (ref "TR9") (pin "5") (pinfunction "NC_5") (pintype "passive"))
    )
    (net (code "49") (name "INPUT_GND") (class "Default")
      (node (ref "FL1") (pin "3") (pinfunction "PSG_3") (pintype "passive"))
      (node (ref "J12") (pin "1") (pinfunction "1_1") (pintype "bidirectional"))
    )
    (net (code "50") (name "Net-(C1-Pad1)") (class "Default")
      (node (ref "C1") (pin "1") (pinfunction "1_1") (pintype "passive"))
      (node (ref "J1") (pin "1") (pinfunction "1_1") (pintype "bidirectional"))
    )
    (net (code "51") (name "Net-(C1-Pad2)") (class "Default")
      (node (ref "C1") (pin "2") (pinfunction "2_2") (pintype "passive"))
      (node (ref "TR2") (pin "3") (pinfunction "P1_3") (pintype "passive"))
    )
    (net (code "52") (name "Net-(C2-Pad1)") (class "Default")
      (node (ref "C2") (pin "1") (pinfunction "1_1") (pintype "passive"))
      (node (ref "C3") (pin "2") (pinfunction "2_2") (pintype "passive"))
      (node (ref "TR2") (pin "6") (pinfunction "S1_6") (pintype "passive"))
    )
    (net (code "53") (name "Net-(C5-Pad1)") (class "Default")
      (node (ref "C5") (pin "1") (pinfunction "1_1") (pintype "passive"))
      (node (ref "C6") (pin "1") (pinfunction "1_1") (pintype "passive"))
      (node (ref "TR2") (pin "4") (pinfunction "S1_4") (pintype "passive"))
    )
    (net (code "54") (name "Net-(C8-Pad1)") (class "Default")
      (node (ref "C8") (pin "1") (pinfunction "1_1") (pintype "passive"))
      (node (ref "J2") (pin "1") (pinfunction "1_1") (pintype "bidirectional"))
    )
    (net (code "55") (name "Net-(C8-Pad2)") (class "Default")
      (node (ref "C8") (pin "2") (pinfunction "2_2") (pintype "passive"))
      (node (ref "TR4") (pin "3") (pinfunction "P1_3") (pintype "passive"))
    )
    (net (code "56") (name "Net-(C10-Pad1)") (class "Default")
      (node (ref "C10") (pin "1") (pinfunction "1_1") (pintype "passive"))
      (node (ref "C11") (pin "1") (pinfunction "1_1") (pintype "passive"))
      (node (ref "TR1") (pin "4") (pinfunction "S1_4") (pintype "passive"))
    )
    (net (code "57") (name "Net-(C12-Pad2)") (class "Default")
      (node (ref "C12") (pin "2") (pinfunction "2_2") (pintype "passive"))
      (node (ref "C9") (pin "1") (pinfunction "1_1") (pintype "passive"))
      (node (ref "TR4") (pin "6") (pinfunction "S1_6") (pintype "passive"))
    )
    (net (code "58") (name "Net-(C14-Pad2)") (class "Default")
      (node (ref "C14") (pin "2") (pinfunction "2_2") (pintype "passive"))
      (node (ref "C18") (pin "1") (pinfunction "1_1") (pintype "passive"))
      (node (ref "TR1") (pin "6") (pinfunction "S1_6") (pintype "passive"))
    )
    (net (code "59") (name "Net-(C15-Pad1)") (class "Default")
      (node (ref "C15") (pin "1") (pinfunction "1_1") (pintype "passive"))
      (node (ref "C16") (pin "1") (pinfunction "1_1") (pintype "passive"))
      (node (ref "TR4") (pin "4") (pinfunction "S1_4") (pintype "passive"))
    )
    (net (code "60") (name "Net-(C19-Pad1)") (class "Default")
      (node (ref "C19") (pin "1") (pinfunction "1_1") (pintype "passive"))
      (node (ref "C20") (pin "1") (pinfunction "1_1") (pintype "passive"))
      (node (ref "TR3") (pin "4") (pinfunction "S1_4") (pintype "passive"))
    )
    (net (code "61") (name "Net-(C21-Pad2)") (class "Default")
      (node (ref "C21") (pin "2") (pinfunction "2_2") (pintype "passive"))
      (node (ref "C22") (pin "1") (pinfunction "1_1") (pintype "passive"))
      (node (ref "TR3") (pin "6") (pinfunction "S1_6") (pintype "passive"))
    )
    (net (code "62") (name "Net-(C24-Pad1)") (class "Default")
      (node (ref "C24") (pin "1") (pinfunction "1_1") (pintype "passive"))
      (node (ref "C25") (pin "1") (pinfunction "1_1") (pintype "passive"))
      (node (ref "TR5") (pin "4") (pinfunction "S1_4") (pintype "passive"))
    )
    (net (code "63") (name "Net-(C27-Pad2)") (class "Default")
      (node (ref "C27") (pin "2") (pinfunction "2_2") (pintype "passive"))
      (node (ref "C29") (pin "1") (pinfunction "1_1") (pintype "passive"))
      (node (ref "TR5") (pin "6") (pinfunction "S1_6") (pintype "passive"))
    )
    (net (code "64") (name "Net-(C31-Pad1)") (class "Default")
      (node (ref "C31") (pin "1") (pinfunction "1_1") (pintype "passive"))
      (node (ref "J3") (pin "1") (pinfunction "1_1") (pintype "bidirectional"))
    )
    (net (code "65") (name "Net-(C32-Pad1)") (class "Default")
      (node (ref "C32") (pin "1") (pinfunction "1_1") (pintype "passive"))
      (node (ref "C34") (pin "1") (pinfunction "1_1") (pintype "passive"))
      (node (ref "TR6") (pin "4") (pinfunction "S1_4") (pintype "passive"))
    )
    (net (code "66") (name "Net-(C35-Pad2)") (class "Default")
      (node (ref "C35") (pin "2") (pinfunction "2_2") (pintype "passive"))
      (node (ref "C37") (pin "1") (pinfunction "1_1") (pintype "passive"))
      (node (ref "TR6") (pin "6") (pinfunction "S1_6") (pintype "passive"))
    )
    (net (code "67") (name "Net-(C38-Pad1)") (class "Default")
      (node (ref "C38") (pin "1") (pinfunction "1_1") (pintype "passive"))
      (node (ref "J4") (pin "1") (pinfunction "1_1") (pintype "bidirectional"))
    )
    (net (code "68") (name "Net-(C40-Pad1)") (class "Default")
      (node (ref "C40") (pin "1") (pinfunction "1_1") (pintype "passive"))
      (node (ref "C41") (pin "1") (pinfunction "1_1") (pintype "passive"))
      (node (ref "TR7") (pin "4") (pinfunction "S1_4") (pintype "passive"))
    )
    (net (code "69") (name "Net-(C48-Pad2)") (class "Default")
      (node (ref "C48") (pin "2") (pinfunction "2_2") (pintype "passive"))
      (node (ref "C51") (pin "1") (pinfunction "1_1") (pintype "passive"))
      (node (ref "TR7") (pin "6") (pinfunction "S1_6") (pintype "passive"))
    )
    (net (code "70") (name "Net-(C50-Pad1)") (class "Default")
      (node (ref "C50") (pin "1") (pinfunction "1_1") (pintype "passive"))
      (node (ref "J5") (pin "1") (pinfunction "1_1") (pintype "bidirectional"))
    )
    (net (code "71") (name "Net-(C53-Pad1)") (class "Default")
      (node (ref "C53") (pin "1") (pinfunction "1_1") (pintype "passive"))
      (node (ref "C54") (pin "1") (pinfunction "1_1") (pintype "passive"))
      (node (ref "TR8") (pin "4") (pinfunction "S1_4") (pintype "passive"))
    )
    (net (code "72") (name "Net-(C55-Pad1)") (class "Default")
      (node (ref "C55") (pin "1") (pinfunction "1_1") (pintype "passive"))
      (node (ref "J6") (pin "1") (pinfunction "1_1") (pintype "bidirectional"))
    )
    (net (code "73") (name "Net-(C57-Pad2)") (class "Default")
      (node (ref "C57") (pin "2") (pinfunction "2_2") (pintype "passive"))
      (node (ref "C59") (pin "1") (pinfunction "1_1") (pintype "passive"))
      (node (ref "TR8") (pin "6") (pinfunction "S1_6") (pintype "passive"))
    )
    (net (code "74") (name "Net-(C60-Pad1)") (class "Default")
      (node (ref "C60") (pin "1") (pinfunction "1_1") (pintype "passive"))
      (node (ref "J7") (pin "1") (pinfunction "1_1") (pintype "bidirectional"))
    )
    (net (code "75") (name "Net-(C62-Pad1)") (class "Default")
      (node (ref "C62") (pin "1") (pinfunction "1_1") (pintype "passive"))
      (node (ref "C63") (pin "1") (pinfunction "1_1") (pintype "passive"))
      (node (ref "TR9") (pin "4") (pinfunction "S1_4") (pintype "passive"))
    )
    (net (code "76") (name "Net-(C65-Pad2)") (class "Default")
      (node (ref "C65") (pin "2") (pinfunction "2_2") (pintype "passive"))
      (node (ref "C66") (pin "1") (pinfunction "1_1") (pintype "passive"))
      (node (ref "TR9") (pin "6") (pinfunction "S1_6") (pintype "passive"))
    )
    (net (code "77") (name "Net-(C67-Pad1)") (class "Default")
      (node (ref "C67") (pin "1") (pinfunction "1_1") (pintype "passive"))
      (node (ref "J8") (pin "1") (pinfunction "1_1") (pintype "bidirectional"))
    )
    (net (code "78") (name "Net-(C70-Pad2)") (class "Default")
      (node (ref "C70") (pin "2") (pinfunction "2_2") (pintype "passive"))
      (node (ref "C71") (pin "2") (pinfunction "2_2") (pintype "passive"))
      (node (ref "IC2") (pin "C1") (pinfunction "VOUT_C1") (pintype "power_in"))
      (node (ref "IC2") (pin "D1") (pinfunction "VOUT_D1") (pintype "power_in"))
      (node (ref "IC2") (pin "D2") (pinfunction "VOUT_D2") (pintype "power_in"))
      (node (ref "IC2") (pin "E1") (pinfunction "VOUT_E1") (pintype "power_in"))
      (node (ref "IC2") (pin "E2") (pinfunction "VOUT_E2") (pintype "power_in"))
      (node (ref "L1") (pin "2") (pinfunction "2_2") (pintype "passive"))
    )
    (net (code "79") (name "Net-(C72-Pad1)") (class "Default")
      (node (ref "C72") (pin "1") (pinfunction "1_1") (pintype "passive"))
      (node (ref "C74") (pin "1") (pinfunction "1_1") (pintype "passive"))
      (node (ref "TR10") (pin "4") (pinfunction "S1_4") (pintype "passive"))
    )
    (net (code "80") (name "Net-(C76-Pad1)") (class "Default")
      (node (ref "C76") (pin "1") (pinfunction "1_1") (pintype "passive"))
      (node (ref "J9") (pin "1") (pinfunction "1_1") (pintype "bidirectional"))
    )
    (net (code "81") (name "Net-(C77-Pad2)") (class "Default")
      (node (ref "C77") (pin "2") (pinfunction "2_2") (pintype "passive"))
      (node (ref "C78") (pin "1") (pinfunction "1_1") (pintype "passive"))
      (node (ref "TR10") (pin "6") (pinfunction "S1_6") (pintype "passive"))
    )
    (net (code "82") (name "Net-(C81-Pad1)") (class "Default")
      (node (ref "C81") (pin "1") (pinfunction "1_1") (pintype "passive"))
      (node (ref "C84") (pin "1") (pinfunction "1_1") (pintype "passive"))
      (node (ref "TR11") (pin "4") (pinfunction "S1_4") (pintype "passive"))
    )
    (net (code "83") (name "Net-(C82-Pad1)") (class "Default")
      (node (ref "C82") (pin "1") (pinfunction "1_1") (pintype "passive"))
      (node (ref "J11") (pin "1") (pinfunction "1_1") (pintype "bidirectional"))
    )
    (net (code "84") (name "Net-(C88-Pad2)") (class "Default")
      (node (ref "C88") (pin "2") (pinfunction "2_2") (pintype "passive"))
      (node (ref "C90") (pin "1") (pinfunction "1_1") (pintype "passive"))
      (node (ref "TR11") (pin "6") (pinfunction "S1_6") (pintype "passive"))
    )
    (net (code "85") (name "Net-(C91-Pad1)") (class "Default")
      (node (ref "C91") (pin "1") (pinfunction "1_1") (pintype "passive"))
      (node (ref "J13") (pin "1") (pinfunction "1_1") (pintype "bidirectional"))
    )
    (net (code "86") (name "Net-(C93-Pad1)") (class "Default")
      (node (ref "C93") (pin "1") (pinfunction "1_1") (pintype "passive"))
      (node (ref "C94") (pin "1") (pinfunction "1_1") (pintype "passive"))
      (node (ref "TR12") (pin "4") (pinfunction "S1_4") (pintype "passive"))
    )
    (net (code "87") (name "Net-(C96-Pad2)") (class "Default")
      (node (ref "C96") (pin "2") (pinfunction "2_2") (pintype "passive"))
      (node (ref "C98") (pin "1") (pinfunction "1_1") (pintype "passive"))
      (node (ref "TR12") (pin "6") (pinfunction "S1_6") (pintype "passive"))
    )
    (net (code "88") (name "Net-(C97-Pad1)") (class "Default")
      (node (ref "C97") (pin "1") (pinfunction "1_1") (pintype "passive"))
      (node (ref "J14") (pin "1") (pinfunction "1_1") (pintype "bidirectional"))
    )
    (net (code "89") (name "Net-(FL1-B)") (class "Default")
      (node (ref "FL1") (pin "1") (pinfunction "B_1") (pintype "passive"))
      (node (ref "J12") (pin "3") (pinfunction "3_3") (pintype "bidirectional"))
    )
    (net (code "90") (name "Net-(IC1-IN_SEL)") (class "Default")
      (node (ref "IC1") (pin "1") (pinfunction "IN_SEL_1") (pintype "input"))
      (node (ref "R10") (pin "2") (pinfunction "2_2") (pintype "passive"))
      (node (ref "R13") (pin "2") (pinfunction "2_2") (pintype "passive"))
      (node (ref "R6") (pin "1") (pinfunction "1_1") (pintype "passive"))
      (node (ref "SW1") (pin "3") (pinfunction "NO_3") (pintype "bidirectional"))
    )
    (net (code "91") (name "Net-(IC1-VREF0)") (class "Default")
      (node (ref "C23") (pin "2") (pinfunction "2_2") (pintype "passive"))
      (node (ref "IC1") (pin "4") (pinfunction "VREF0_4") (pintype "input"))
      (node (ref "IC1") (pin "5") (pinfunction "VT0_5") (pintype "passive"))
    )
    (net (code "92") (name "Net-(IC1-VREF1)") (class "Default")
      (node (ref "C28") (pin "2") (pinfunction "2_2") (pintype "passive"))
      (node (ref "IC1") (pin "8") (pinfunction "VT1_8") (pintype "passive"))
      (node (ref "IC1") (pin "9") (pinfunction "VREF1_9") (pintype "input"))
    )
    (net (code "93") (name "Net-(IC2-COMP)") (class "Default")
      (node (ref "IC2") (pin "A1") (pinfunction "COMP_A1") (pintype "input"))
      (node (ref "TP2") (pin "1") (pinfunction "1_1") (pintype "bidirectional"))
    )
    (net (code "94") (name "Net-(IC2-FB)") (class "Default")
      (node (ref "IC2") (pin "B1") (pinfunction "FB_B1") (pintype "input"))
      (node (ref "R35") (pin "1") (pinfunction "1_1") (pintype "passive"))
    )
    (net (code "95") (name "Net-(IC2-FREQ)") (class "Default")
      (node (ref "IC2") (pin "A4") (pinfunction "FREQ_A4") (pintype "input"))
      (node (ref "TP1") (pin "1") (pinfunction "1_1") (pintype "bidirectional"))
    )
    (net (code "96") (name "Net-(IC2-INTVCC)") (class "Default")
      (node (ref "IC2") (pin "C4") (pinfunction "MODE_C4") (pintype "input"))
      (node (ref "IC2") (pin "E4") (pinfunction "INTVCC_E4") (pintype "power_in"))
    )
    (net (code "97") (name "Net-(IC2-TRACK{slash}SS)") (class "Default")
      (node (ref "C80") (pin "2") (pinfunction "2_2") (pintype "passive"))
      (node (ref "IC2") (pin "A2") (pinfunction "TRACK/SS_A2") (pintype "input"))
    )
    (net (code "98") (name "Net-(IC3-SET)") (class "Default")
      (node (ref "C101") (pin "1") (pinfunction "1_1") (pintype "passive"))
      (node (ref "IC3") (pin "7") (pinfunction "SET_7") (pintype "input"))
      (node (ref "R39") (pin "1") (pinfunction "1_1") (pintype "passive"))
    )
    (net (code "99") (name "Net-(LD1B-A)") (class "Default")
      (node (ref "LD1") (pin "4") (pinfunction "A_4") (pintype "passive"))
      (node (ref "R10") (pin "1") (pinfunction "1_1") (pintype "passive"))
      (node (ref "R13") (pin "1") (pinfunction "1_1") (pintype "passive"))
    )
    (net (code "100") (name "P3V3") (class "Default")
      (node (ref "B4") (pin "1") (pinfunction "1_1") (pintype "bidirectional"))
      (node (ref "C100") (pin "2") (pinfunction "2_2") (pintype "passive"))
      (node (ref "C42") (pin "2") (pinfunction "2_2") (pintype "passive"))
      (node (ref "C43") (pin "2") (pinfunction "2_2") (pintype "passive"))
      (node (ref "C44") (pin "2") (pinfunction "2_2") (pintype "passive"))
      (node (ref "C45") (pin "2") (pinfunction "2_2") (pintype "passive"))
      (node (ref "C46") (pin "2") (pinfunction "2_2") (pintype "passive"))
      (node (ref "IC1") (pin "11") (pinfunction "VCC_11") (pintype "power_in"))
      (node (ref "IC1") (pin "20") (pinfunction "VCC_20") (pintype "power_in"))
      (node (ref "IC1") (pin "21") (pinfunction "VCC_21") (pintype "power_in"))
      (node (ref "IC1") (pin "30") (pinfunction "VCC_30") (pintype "power_in"))
      (node (ref "IC1") (pin "31") (pinfunction "VCC_31") (pintype "power_in"))
      (node (ref "IC1") (pin "40") (pinfunction "VCC_40") (pintype "power_in"))
      (node (ref "IC3") (pin "10") (pinfunction "OUT_10") (pintype "output"))
      (node (ref "IC3") (pin "9") (pinfunction "OUTS_9") (pintype "output"))
      (node (ref "R16") (pin "2") (pinfunction "2_2") (pintype "passive"))
      (node (ref "R18") (pin "2") (pinfunction "2_2") (pintype "passive"))
      (node (ref "SW1") (pin "2") (pinfunction "C_2") (pintype "bidirectional"))
    )
    (net (code "101") (name "P3V6") (class "Default")
      (node (ref "C85") (pin "1") (pinfunction "1_1") (pintype "passive"))
      (node (ref "C86") (pin "2") (pinfunction "2_2") (pintype "passive"))
      (node (ref "C99") (pin "1") (pinfunction "1_1") (pintype "passive"))
      (node (ref "IC3") (pin "1") (pinfunction "IN_1") (pintype "input"))
      (node (ref "IC3") (pin "2") (pinfunction "IN_2") (pintype "input"))
      (node (ref "IC3") (pin "3") (pinfunction "EN/UV_3") (pintype "input"))
      (node (ref "IC3") (pin "6") (pinfunction "PGFB_6") (pintype "input"))
      (node (ref "L1") (pin "1") (pinfunction "1_1") (pintype "passive"))
    )
    (net (code "102") (name "P12V0") (class "Default")
      (node (ref "B5") (pin "1") (pinfunction "1_1") (pintype "bidirectional"))
      (node (ref "C69") (pin "2") (pinfunction "2_2") (pintype "passive"))
      (node (ref "C87") (pin "1") (pinfunction "1_1") (pintype "passive"))
      (node (ref "D1") (pin "1") (pinfunction "C_1") (pintype "passive"))
      (node (ref "FL1") (pin "2") (pinfunction "CB_2") (pintype "passive"))
      (node (ref "IC2") (pin "A3") (pinfunction "RUN_A3") (pintype "input"))
      (node (ref "IC2") (pin "C5") (pinfunction "SVIN_C5") (pintype "power_in"))
      (node (ref "IC2") (pin "D5") (pinfunction "VIN_D5") (pintype "power_in"))
      (node (ref "IC2") (pin "E5") (pinfunction "VIN_E5") (pintype "power_in"))
      (node (ref "J10") (pin "28") (pinfunction "28_28") (pintype "bidirectional"))
      (node (ref "J10") (pin "29") (pinfunction "29_29") (pintype "bidirectional"))
    )
    (net (code "103") (name "unconnected-(IC1-NC-Pad22)") (class "Default")
      (node (ref "IC1") (pin "22") (pinfunction "NC_22") (pintype "passive"))
    )
    (net (code "104") (name "unconnected-(IC1-NC-Pad23)") (class "Default")
      (node (ref "IC1") (pin "23") (pinfunction "NC_23") (pintype "passive"))
    )
    (net (code "105") (name "unconnected-(IC1-NC-Pad28)") (class "Default")
      (node (ref "IC1") (pin "28") (pinfunction "NC_28") (pintype "passive"))
    )
    (net (code "106") (name "unconnected-(IC1-NC-Pad29)") (class "Default")
      (node (ref "IC1") (pin "29") (pinfunction "NC_29") (pintype "passive"))
    )
    (net (code "107") (name "unconnected-(IC2-CLKIN-PadA5)") (class "Default")
      (node (ref "IC2") (pin "A5") (pinfunction "CLKIN_A5") (pintype "input+no_connect"))
    )
    (net (code "108") (name "unconnected-(IC2-CLKOUT-PadB5)") (class "Default")
      (node (ref "IC2") (pin "B5") (pinfunction "CLKOUT_B5") (pintype "output+no_connect"))
    )
    (net (code "109") (name "unconnected-(IC2-PHMODE-PadB2)") (class "Default")
      (node (ref "IC2") (pin "B2") (pinfunction "PHMODE_B2") (pintype "input"))
    )
    (net (code "110") (name "unconnected-(J10-Pad2)") (class "Default")
      (node (ref "J10") (pin "2") (pinfunction "2_2") (pintype "bidirectional"))
    )
    (net (code "111") (name "unconnected-(J10-Pad3)") (class "Default")
      (node (ref "J10") (pin "3") (pinfunction "3_3") (pintype "bidirectional"))
    )
    (net (code "112") (name "unconnected-(J10-Pad5)") (class "Default")
      (node (ref "J10") (pin "5") (pinfunction "5_5") (pintype "bidirectional"))
    )
    (net (code "113") (name "unconnected-(J10-Pad6)") (class "Default")
      (node (ref "J10") (pin "6") (pinfunction "6_6") (pintype "bidirectional"))
    )
    (net (code "114") (name "unconnected-(J10-Pad8)") (class "Default")
      (node (ref "J10") (pin "8") (pinfunction "8_8") (pintype "bidirectional"))
    )
    (net (code "115") (name "unconnected-(J10-Pad9)") (class "Default")
      (node (ref "J10") (pin "9") (pinfunction "9_9") (pintype "bidirectional"))
    )
    (net (code "116") (name "unconnected-(J10-Pad11)") (class "Default")
      (node (ref "J10") (pin "11") (pinfunction "11_11") (pintype "bidirectional"))
    )
    (net (code "117") (name "unconnected-(J10-Pad12)") (class "Default")
      (node (ref "J10") (pin "12") (pinfunction "12_12") (pintype "bidirectional"))
    )
    (net (code "118") (name "unconnected-(J10-Pad14)") (class "Default")
      (node (ref "J10") (pin "14") (pinfunction "14_14") (pintype "bidirectional"))
    )
    (net (code "119") (name "unconnected-(J10-Pad15)") (class "Default")
      (node (ref "J10") (pin "15") (pinfunction "15_15") (pintype "bidirectional"))
    )
    (net (code "120") (name "unconnected-(J10-Pad17)") (class "Default")
      (node (ref "J10") (pin "17") (pinfunction "17_17") (pintype "bidirectional"))
    )
    (net (code "121") (name "unconnected-(J10-Pad18)") (class "Default")
      (node (ref "J10") (pin "18") (pinfunction "18_18") (pintype "bidirectional"))
    )
    (net (code "122") (name "unconnected-(J10-Pad20)") (class "Default")
      (node (ref "J10") (pin "20") (pinfunction "20_20") (pintype "bidirectional"))
    )
    (net (code "123") (name "unconnected-(J10-Pad21)") (class "Default")
      (node (ref "J10") (pin "21") (pinfunction "21_21") (pintype "bidirectional"))
    )
    (net (code "124") (name "unconnected-(J10-Pad23)") (class "Default")
      (node (ref "J10") (pin "23") (pinfunction "23_23") (pintype "bidirectional"))
    )
    (net (code "125") (name "unconnected-(J10-Pad24)") (class "Default")
      (node (ref "J10") (pin "24") (pinfunction "24_24") (pintype "bidirectional"))
    )
    (net (code "126") (name "unconnected-(J10-Pad26)") (class "Default")
      (node (ref "J10") (pin "26") (pinfunction "26_26") (pintype "bidirectional"))
    )
    (net (code "127") (name "unconnected-(J10-Pad27)") (class "Default")
      (node (ref "J10") (pin "27") (pinfunction "27_27") (pintype "bidirectional"))
    )
    (net (code "128") (name "unconnected-(J10-Pad30)") (class "Default")
      (node (ref "J10") (pin "30") (pinfunction "30_30") (pintype "bidirectional"))
    )
    (net (code "129") (name "unconnected-(J12-Pad2)") (class "Default")
      (node (ref "J12") (pin "2") (pinfunction "2_2") (pintype "bidirectional"))
    )
    (net (code "130") (name "unconnected-(SW1-NC-Pad1)") (class "Default")
      (node (ref "SW1") (pin "1") (pinfunction "NC_1") (pintype "bidirectional"))
    )
  )
)
